# QI9-2605-A01.net
KiCad netlist of a schematic drawn in Altium Designer
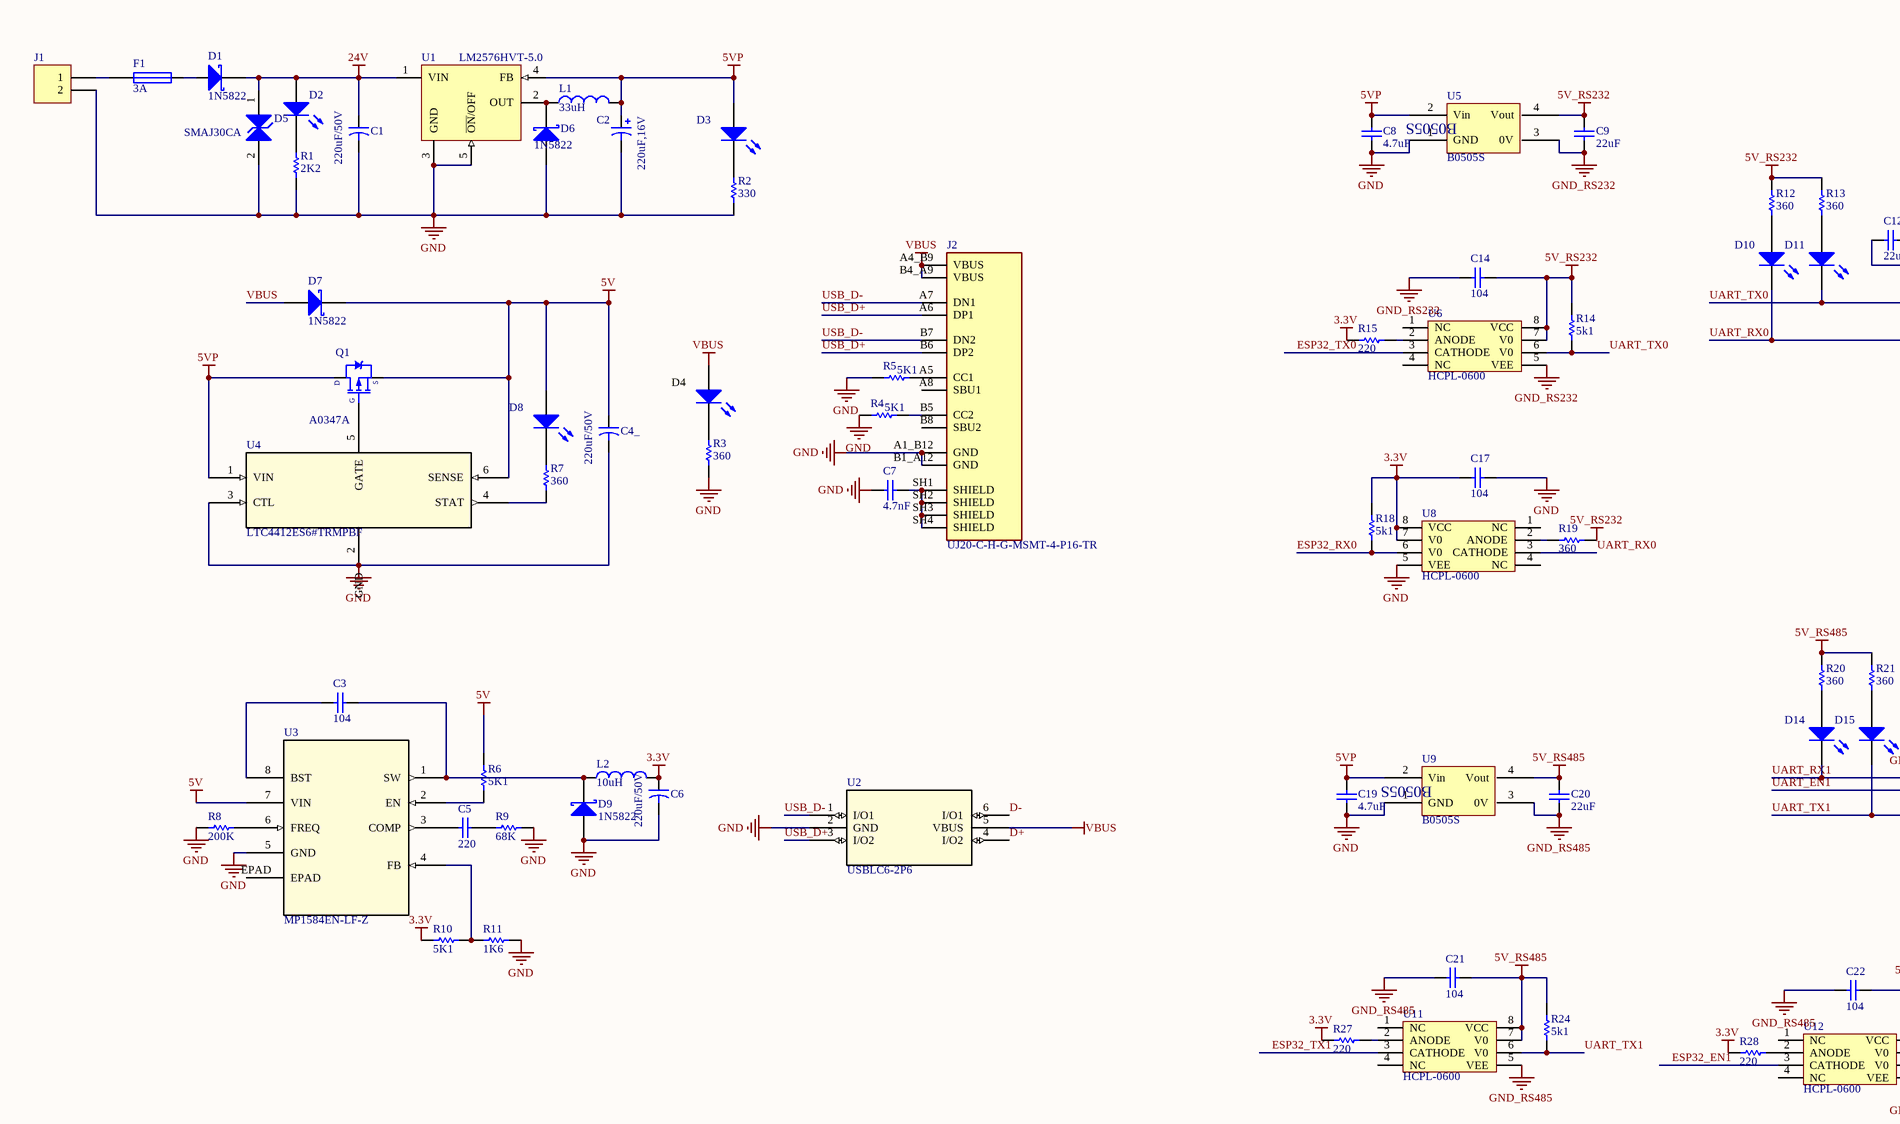
[diagram p0: QI9-2605-A01_.SchDoc, top left]
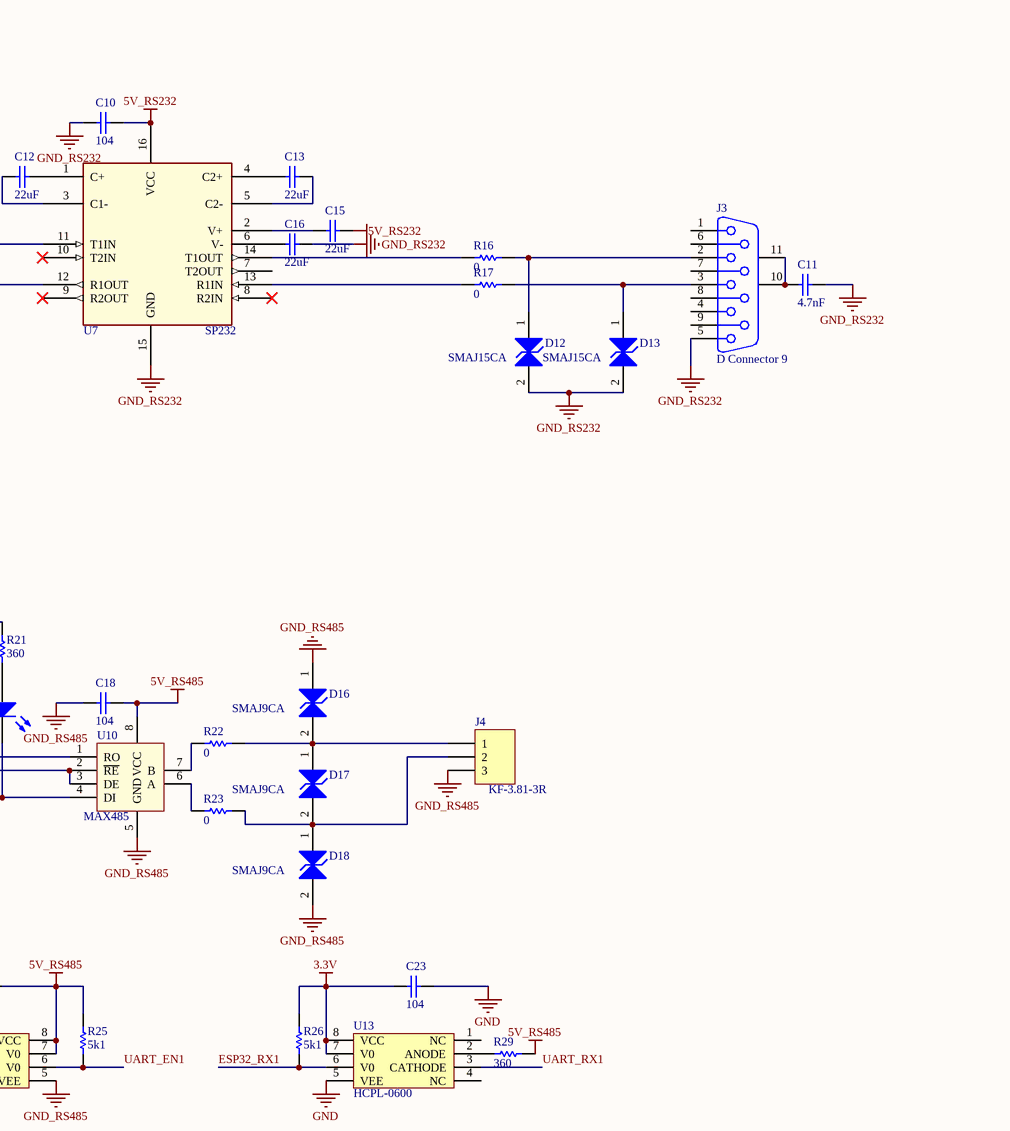
[diagram p1: QI9-2605-A01_.SchDoc, top right]
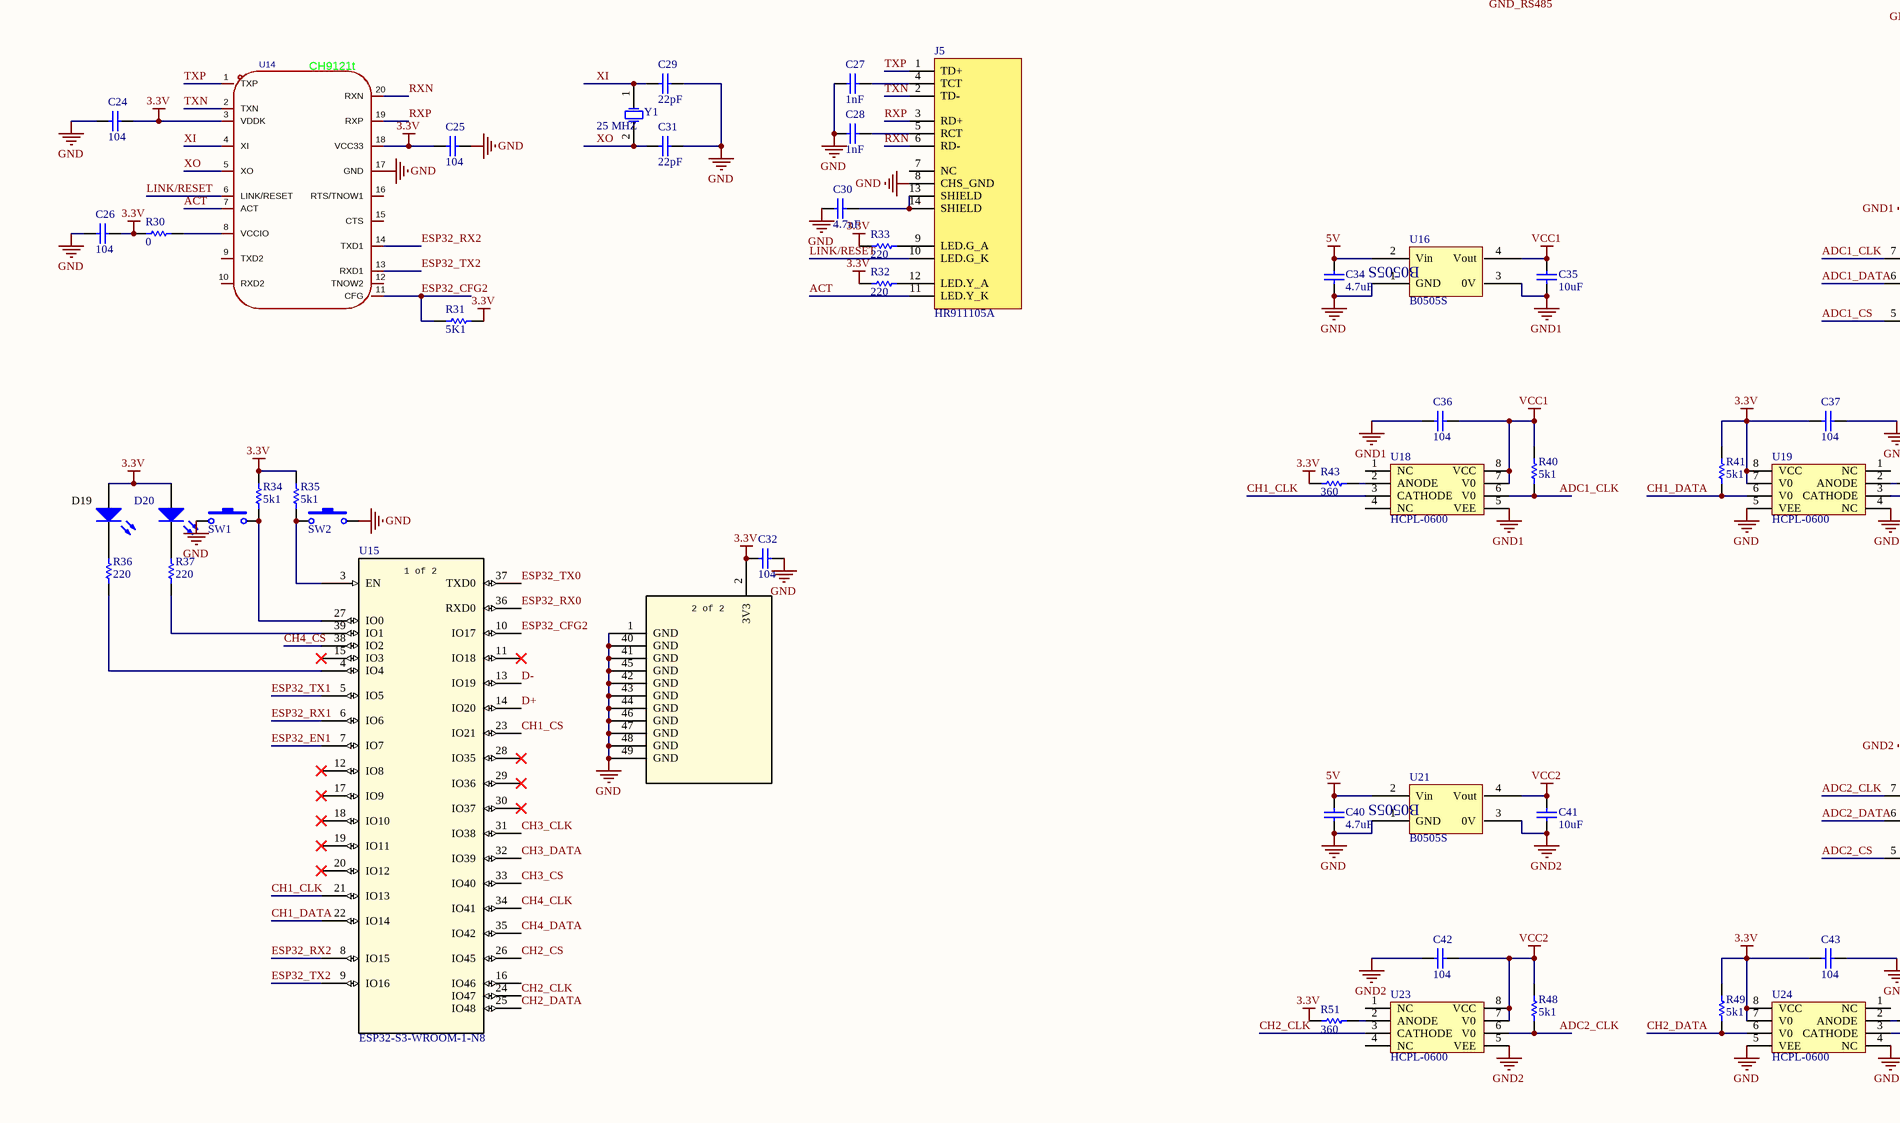
[diagram p2: QI9-2605-A01_.SchDoc, bottom left]
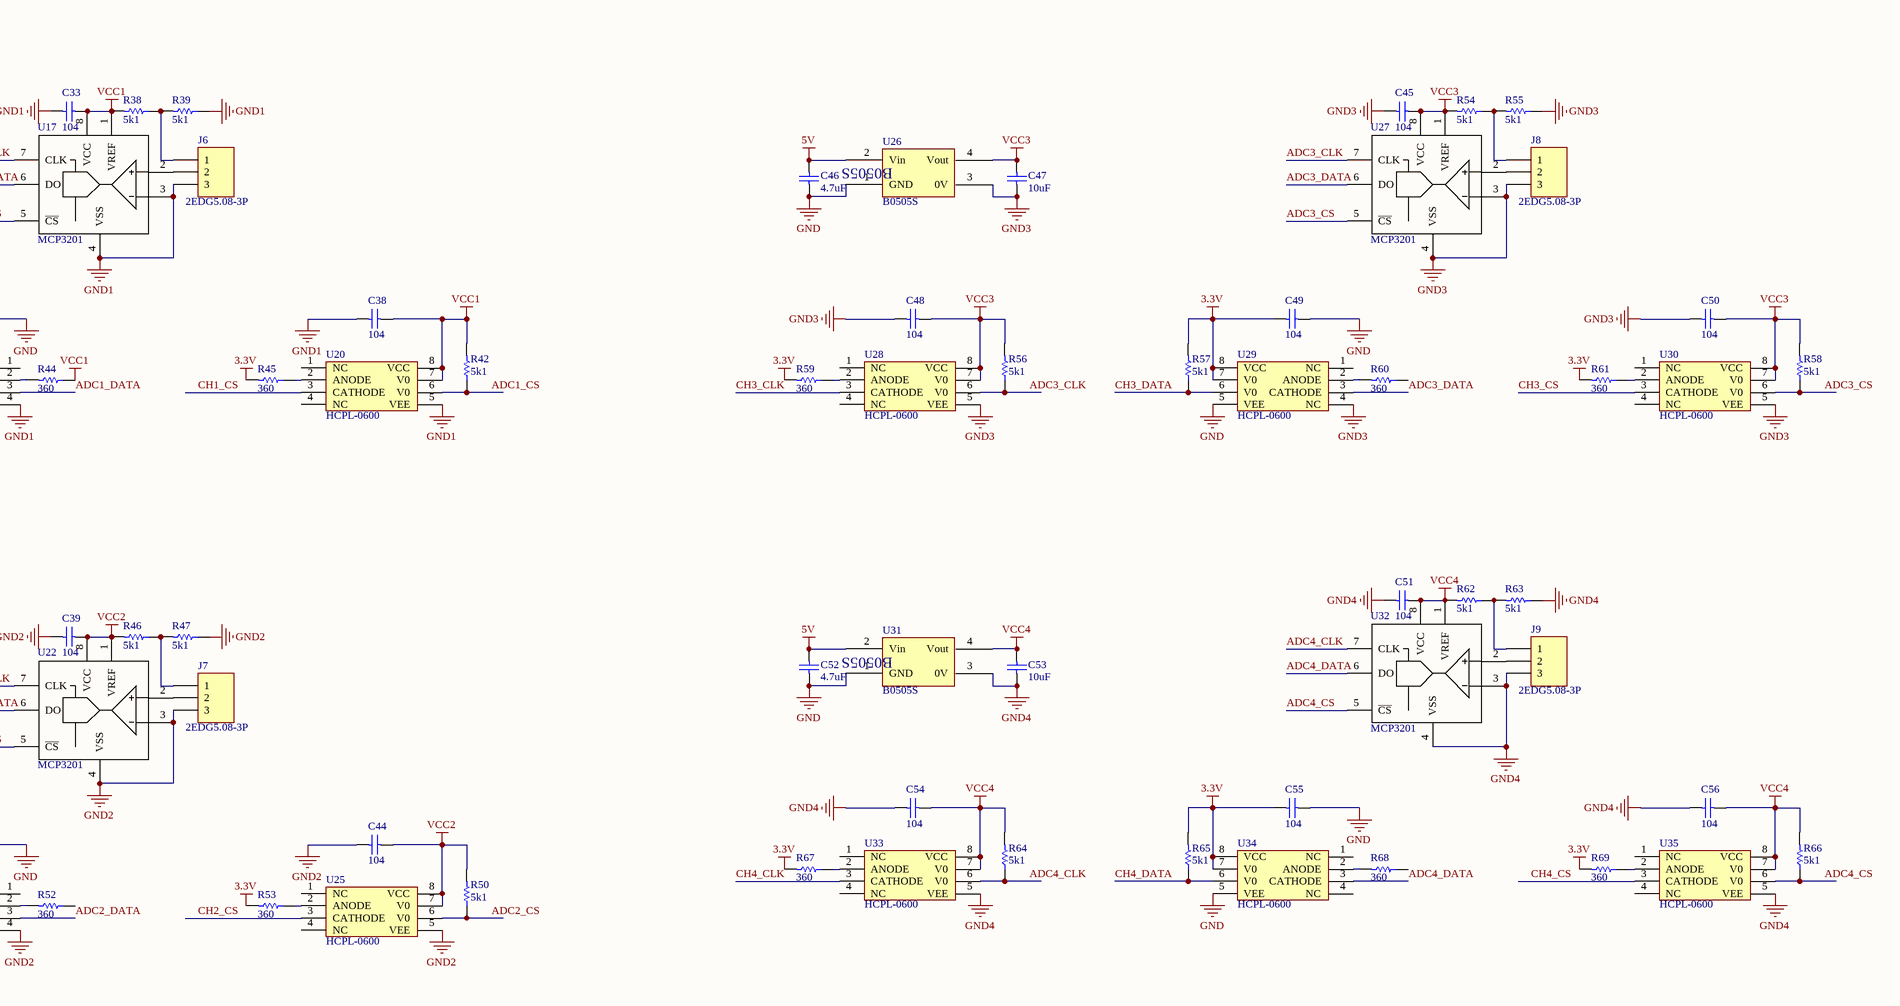
[diagram p3: QI9-2605-A01_.SchDoc, bottom right]

(export (version "E")
  (design (tool "Eeschema 10.0.6"))
  (components
    (comp (ref "C1")
      (value "220uF/50V")
      (footprint "C2")
      (description "Capacitor")
      (fields (field (name "Comment") "Cap2") (field (name "PUBLISHER") "Altium Limited"))
      (libsource (lib "Miscellaneous Devices") (part "Cap2"))
    )
    (comp (ref "C2")
      (value "220uF,16V")
      (footprint "c2")
      (description "Polarized Capacitor (Axial)")
      (fields (field (name "PUBLISHER") "Altium Limited"))
      (libsource (lib "StandardLIB") (part "Cap Pol 3mm"))
    )
    (comp (ref "C3")
      (value "104")
      (footprint "0805")
      (description "Capacitor")
      (fields (field (name "Comment") "Cap") (field (name "PUBLISHER") "Altium Limited"))
      (libsource (lib "Miscellaneous Devices") (part "Cap"))
    )
    (comp (ref "C4_")
      (value "220uF/50V")
      (footprint "C2")
      (description "Capacitor")
      (fields (field (name "Comment") "Cap2") (field (name "PUBLISHER") "Altium Limited"))
      (libsource (lib "Miscellaneous Devices") (part "Cap2"))
    )
    (comp (ref "C5")
      (value "220")
      (footprint "0805")
      (description "Capacitor")
      (fields (field (name "Comment") "Cap") (field (name "PUBLISHER") "Altium Limited"))
      (libsource (lib "Miscellaneous Devices") (part "Cap"))
    )
    (comp (ref "C6")
      (value "220uF/50V")
      (footprint "C2")
      (description "Capacitor")
      (fields (field (name "Comment") "Cap2") (field (name "PUBLISHER") "Altium Limited"))
      (libsource (lib "Miscellaneous Devices") (part "Cap2"))
    )
    (comp (ref "C7")
      (value "4.7nF")
      (footprint "0805")
      (description "Capacitor")
      (fields (field (name "Comment") "Cap") (field (name "PUBLISHER") "Altium Limited"))
      (libsource (lib "Miscellaneous Devices") (part "Cap"))
    )
    (comp (ref "C8")
      (value "4.7uF")
      (footprint "CP1/2")
      (description "Capacitor")
      (fields (field (name "Comment") "Cap") (field (name "PUBLISHER") "Altium Limited"))
      (libsource (lib "Miscellaneous Devices") (part "Cap"))
    )
    (comp (ref "C9")
      (value "22uF")
      (footprint "0805")
      (description "Capacitor")
      (fields (field (name "Comment") "Cap") (field (name "PUBLISHER") "Altium Limited"))
      (libsource (lib "Miscellaneous Devices") (part "Cap"))
    )
    (comp (ref "C10")
      (value "104")
      (footprint "0805")
      (description "Capacitor")
      (fields (field (name "Comment") "Cap") (field (name "PUBLISHER") "Altium Limited"))
      (libsource (lib "Miscellaneous Devices") (part "Cap"))
    )
    (comp (ref "C11")
      (value "4.7nF")
      (footprint "0805")
      (description "Capacitor")
      (fields (field (name "Comment") "Cap") (field (name "PUBLISHER") "Altium Limited"))
      (libsource (lib "Miscellaneous Devices") (part "Cap"))
    )
    (comp (ref "C12")
      (value "22uF")
      (footprint "0805")
      (description "Capacitor")
      (fields (field (name "Comment") "Cap") (field (name "PUBLISHER") "Altium Limited"))
      (libsource (lib "Miscellaneous Devices") (part "Cap"))
    )
    (comp (ref "C13")
      (value "22uF")
      (footprint "0805")
      (description "Capacitor")
      (fields (field (name "Comment") "Cap") (field (name "PUBLISHER") "Altium Limited"))
      (libsource (lib "Miscellaneous Devices") (part "Cap"))
    )
    (comp (ref "C14")
      (value "104")
      (footprint "0805")
      (description "Capacitor")
      (fields (field (name "Comment") "Cap") (field (name "PUBLISHER") "Altium Limited"))
      (libsource (lib "Miscellaneous Devices") (part "Cap"))
    )
    (comp (ref "C15")
      (value "22uF")
      (footprint "0805")
      (description "Capacitor")
      (fields (field (name "Comment") "Cap") (field (name "PUBLISHER") "Altium Limited"))
      (libsource (lib "Miscellaneous Devices") (part "Cap"))
    )
    (comp (ref "C16")
      (value "22uF")
      (footprint "0805")
      (description "Capacitor")
      (fields (field (name "Comment") "Cap") (field (name "PUBLISHER") "Altium Limited"))
      (libsource (lib "Miscellaneous Devices") (part "Cap"))
    )
    (comp (ref "C17")
      (value "104")
      (footprint "0805")
      (description "Capacitor")
      (fields (field (name "Comment") "Cap") (field (name "PUBLISHER") "Altium Limited"))
      (libsource (lib "Miscellaneous Devices") (part "Cap"))
    )
    (comp (ref "C18")
      (value "104")
      (footprint "0805")
      (description "Capacitor")
      (fields (field (name "Comment") "Cap") (field (name "PUBLISHER") "Altium Limited"))
      (libsource (lib "Miscellaneous Devices") (part "Cap"))
    )
    (comp (ref "C19")
      (value "4.7uF")
      (footprint "CP1/2")
      (description "Capacitor")
      (fields (field (name "Comment") "Cap") (field (name "PUBLISHER") "Altium Limited"))
      (libsource (lib "Miscellaneous Devices") (part "Cap"))
    )
    (comp (ref "C20")
      (value "22uF")
      (footprint "0805")
      (description "Capacitor")
      (fields (field (name "Comment") "Cap") (field (name "PUBLISHER") "Altium Limited"))
      (libsource (lib "Miscellaneous Devices") (part "Cap"))
    )
    (comp (ref "C21")
      (value "104")
      (footprint "0805")
      (description "Capacitor")
      (fields (field (name "Comment") "Cap") (field (name "PUBLISHER") "Altium Limited"))
      (libsource (lib "Miscellaneous Devices") (part "Cap"))
    )
    (comp (ref "C22")
      (value "104")
      (footprint "0805")
      (description "Capacitor")
      (fields (field (name "Comment") "Cap") (field (name "PUBLISHER") "Altium Limited"))
      (libsource (lib "Miscellaneous Devices") (part "Cap"))
    )
    (comp (ref "C23")
      (value "104")
      (footprint "0805")
      (description "Capacitor")
      (fields (field (name "Comment") "Cap") (field (name "PUBLISHER") "Altium Limited"))
      (libsource (lib "Miscellaneous Devices") (part "Cap"))
    )
    (comp (ref "C24")
      (value "104")
      (footprint "0805")
      (description "Capacitor")
      (fields (field (name "Comment") "Cap") (field (name "PUBLISHER") "Altium Limited"))
      (libsource (lib "Miscellaneous Devices") (part "Cap"))
    )
    (comp (ref "C25")
      (value "104")
      (footprint "0805")
      (description "Capacitor")
      (fields (field (name "Comment") "Cap") (field (name "PUBLISHER") "Altium Limited"))
      (libsource (lib "Miscellaneous Devices") (part "Cap"))
    )
    (comp (ref "C26")
      (value "104")
      (footprint "0805")
      (description "Capacitor")
      (fields (field (name "Comment") "Cap") (field (name "PUBLISHER") "Altium Limited"))
      (libsource (lib "Miscellaneous Devices") (part "Cap"))
    )
    (comp (ref "C27")
      (value "1nF")
      (footprint "0805")
      (description "Capacitor")
      (fields (field (name "Comment") "Cap") (field (name "PUBLISHER") "Altium Limited"))
      (libsource (lib "Miscellaneous Devices") (part "Cap"))
    )
    (comp (ref "C28")
      (value "1nF")
      (footprint "0805")
      (description "Capacitor")
      (fields (field (name "Comment") "Cap") (field (name "PUBLISHER") "Altium Limited"))
      (libsource (lib "Miscellaneous Devices") (part "Cap"))
    )
    (comp (ref "C29")
      (value "22pF")
      (footprint "0805")
      (description "Capacitor")
      (fields (field (name "Comment") "Cap") (field (name "PUBLISHER") "Altium Limited"))
      (libsource (lib "Miscellaneous Devices") (part "Cap"))
    )
    (comp (ref "C30")
      (value "4.7nF")
      (footprint "0805")
      (description "Capacitor")
      (fields (field (name "Comment") "Cap") (field (name "PUBLISHER") "Altium Limited"))
      (libsource (lib "Miscellaneous Devices") (part "Cap"))
    )
    (comp (ref "C31")
      (value "22pF")
      (footprint "0805")
      (description "Capacitor")
      (fields (field (name "Comment") "Cap") (field (name "PUBLISHER") "Altium Limited"))
      (libsource (lib "Miscellaneous Devices") (part "Cap"))
    )
    (comp (ref "C32")
      (value "104")
      (footprint "0805")
      (description "Capacitor")
      (fields (field (name "Comment") "Cap") (field (name "PUBLISHER") "Altium Limited"))
      (libsource (lib "Miscellaneous Devices") (part "Cap"))
    )
    (comp (ref "C33")
      (value "104")
      (footprint "0805")
      (description "Capacitor")
      (fields (field (name "Comment") "Cap") (field (name "PUBLISHER") "Altium Limited"))
      (libsource (lib "Miscellaneous Devices") (part "Cap"))
    )
    (comp (ref "C34")
      (value "4.7uF")
      (footprint "CP1/2")
      (description "Capacitor")
      (fields (field (name "Comment") "Cap") (field (name "PUBLISHER") "Altium Limited"))
      (libsource (lib "Miscellaneous Devices") (part "Cap"))
    )
    (comp (ref "C35")
      (value "10uF")
      (footprint "CP1/2")
      (description "Capacitor")
      (fields (field (name "Comment") "Cap") (field (name "PUBLISHER") "Altium Limited"))
      (libsource (lib "Miscellaneous Devices") (part "Cap"))
    )
    (comp (ref "C36")
      (value "104")
      (footprint "0805")
      (description "Capacitor")
      (fields (field (name "Comment") "Cap") (field (name "PUBLISHER") "Altium Limited"))
      (libsource (lib "Miscellaneous Devices") (part "Cap"))
    )
    (comp (ref "C37")
      (value "104")
      (footprint "0805")
      (description "Capacitor")
      (fields (field (name "Comment") "Cap") (field (name "PUBLISHER") "Altium Limited"))
      (libsource (lib "Miscellaneous Devices") (part "Cap"))
    )
    (comp (ref "C38")
      (value "104")
      (footprint "0805")
      (description "Capacitor")
      (fields (field (name "Comment") "Cap") (field (name "PUBLISHER") "Altium Limited"))
      (libsource (lib "Miscellaneous Devices") (part "Cap"))
    )
    (comp (ref "C39")
      (value "104")
      (footprint "0805")
      (description "Capacitor")
      (fields (field (name "Comment") "Cap") (field (name "PUBLISHER") "Altium Limited"))
      (libsource (lib "Miscellaneous Devices") (part "Cap"))
    )
    (comp (ref "C40")
      (value "4.7uF")
      (footprint "CP1/2")
      (description "Capacitor")
      (fields (field (name "Comment") "Cap") (field (name "PUBLISHER") "Altium Limited"))
      (libsource (lib "Miscellaneous Devices") (part "Cap"))
    )
    (comp (ref "C41")
      (value "10uF")
      (footprint "CP1/2")
      (description "Capacitor")
      (fields (field (name "Comment") "Cap") (field (name "PUBLISHER") "Altium Limited"))
      (libsource (lib "Miscellaneous Devices") (part "Cap"))
    )
    (comp (ref "C42")
      (value "104")
      (footprint "0805")
      (description "Capacitor")
      (fields (field (name "Comment") "Cap") (field (name "PUBLISHER") "Altium Limited"))
      (libsource (lib "Miscellaneous Devices") (part "Cap"))
    )
    (comp (ref "C43")
      (value "104")
      (footprint "0805")
      (description "Capacitor")
      (fields (field (name "Comment") "Cap") (field (name "PUBLISHER") "Altium Limited"))
      (libsource (lib "Miscellaneous Devices") (part "Cap"))
    )
    (comp (ref "C44")
      (value "104")
      (footprint "0805")
      (description "Capacitor")
      (fields (field (name "Comment") "Cap") (field (name "PUBLISHER") "Altium Limited"))
      (libsource (lib "Miscellaneous Devices") (part "Cap"))
    )
    (comp (ref "C45")
      (value "104")
      (footprint "0805")
      (description "Capacitor")
      (fields (field (name "Comment") "Cap") (field (name "PUBLISHER") "Altium Limited"))
      (libsource (lib "Miscellaneous Devices") (part "Cap"))
    )
    (comp (ref "C46")
      (value "4.7uF")
      (footprint "CP1/2")
      (description "Capacitor")
      (fields (field (name "Comment") "Cap") (field (name "PUBLISHER") "Altium Limited"))
      (libsource (lib "Miscellaneous Devices") (part "Cap"))
    )
    (comp (ref "C47")
      (value "10uF")
      (footprint "CP1/2")
      (description "Capacitor")
      (fields (field (name "Comment") "Cap") (field (name "PUBLISHER") "Altium Limited"))
      (libsource (lib "Miscellaneous Devices") (part "Cap"))
    )
    (comp (ref "C48")
      (value "104")
      (footprint "0805")
      (description "Capacitor")
      (fields (field (name "Comment") "Cap") (field (name "PUBLISHER") "Altium Limited"))
      (libsource (lib "Miscellaneous Devices") (part "Cap"))
    )
    (comp (ref "C49")
      (value "104")
      (footprint "0805")
      (description "Capacitor")
      (fields (field (name "Comment") "Cap") (field (name "PUBLISHER") "Altium Limited"))
      (libsource (lib "Miscellaneous Devices") (part "Cap"))
    )
    (comp (ref "C50")
      (value "104")
      (footprint "0805")
      (description "Capacitor")
      (fields (field (name "Comment") "Cap") (field (name "PUBLISHER") "Altium Limited"))
      (libsource (lib "Miscellaneous Devices") (part "Cap"))
    )
    (comp (ref "C51")
      (value "104")
      (footprint "0805")
      (description "Capacitor")
      (fields (field (name "Comment") "Cap") (field (name "PUBLISHER") "Altium Limited"))
      (libsource (lib "Miscellaneous Devices") (part "Cap"))
    )
    (comp (ref "C52")
      (value "4.7uF")
      (footprint "CP1/2")
      (description "Capacitor")
      (fields (field (name "Comment") "Cap") (field (name "PUBLISHER") "Altium Limited"))
      (libsource (lib "Miscellaneous Devices") (part "Cap"))
    )
    (comp (ref "C53")
      (value "10uF")
      (footprint "CP1/2")
      (description "Capacitor")
      (fields (field (name "Comment") "Cap") (field (name "PUBLISHER") "Altium Limited"))
      (libsource (lib "Miscellaneous Devices") (part "Cap"))
    )
    (comp (ref "C54")
      (value "104")
      (footprint "0805")
      (description "Capacitor")
      (fields (field (name "Comment") "Cap") (field (name "PUBLISHER") "Altium Limited"))
      (libsource (lib "Miscellaneous Devices") (part "Cap"))
    )
    (comp (ref "C55")
      (value "104")
      (footprint "0805")
      (description "Capacitor")
      (fields (field (name "Comment") "Cap") (field (name "PUBLISHER") "Altium Limited"))
      (libsource (lib "Miscellaneous Devices") (part "Cap"))
    )
    (comp (ref "C56")
      (value "104")
      (footprint "0805")
      (description "Capacitor")
      (fields (field (name "Comment") "Cap") (field (name "PUBLISHER") "Altium Limited"))
      (libsource (lib "Miscellaneous Devices") (part "Cap"))
    )
    (comp (ref "D1")
      (value "1N5822")
      (footprint "DIODE_DO214AC_SMA")
      (description "Schottky Diode")
      (fields (field (name "PUBLISHER") "Altium Limited"))
      (libsource (lib "Miscellaneous Devices") (part "D Schottky"))
    )
    (comp (ref "D2")
      (value "LED")
      (footprint "LED_0805_RED")
      (description "Typical INFRARED GaAs LED")
      (fields (field (name "PUBLISHER") "Altium Limited"))
      (libsource (lib "Miscellaneous Devices") (part "LED0"))
    )
    (comp (ref "D3")
      (value "LED")
      (footprint "LED_0805_RED")
      (description "Typical INFRARED GaAs LED")
      (fields (field (name "PUBLISHER") "Altium Limited"))
      (libsource (lib "Miscellaneous Devices") (part "LED0"))
    )
    (comp (ref "D4")
      (value "LED")
      (footprint "LED_0805_RED")
      (description "Typical INFRARED GaAs LED")
      (fields (field (name "PUBLISHER") "Altium Limited"))
      (libsource (lib "Miscellaneous Devices") (part "LED0"))
    )
    (comp (ref "D5")
      (value "SMAJ30CA")
      (footprint "SMA_STM")
      (description "TVS DIODE 30V 48.4V DO214AC")
      (fields (field (name "MPN") "SMAJ30A") (field (name "MFR") "Littelfuse Inc."))
      (libsource (lib "Cty1") (part "SMAJ30CA"))
    )
    (comp (ref "D6")
      (value "1N5822")
      (footprint "DIODE_DO214AC_SMA")
      (description "Schottky Diode")
      (fields (field (name "PUBLISHER") "Altium Limited"))
      (libsource (lib "Miscellaneous Devices") (part "D Schottky"))
    )
    (comp (ref "D7")
      (value "1N5822")
      (footprint "DIODE_DO214AC_SMA")
      (description "Schottky Diode")
      (fields (field (name "PUBLISHER") "Altium Limited"))
      (libsource (lib "Miscellaneous Devices") (part "D Schottky"))
    )
    (comp (ref "D8")
      (value "LED")
      (footprint "LED_0805_RED")
      (description "Typical INFRARED GaAs LED")
      (fields (field (name "PUBLISHER") "Altium Limited"))
      (libsource (lib "Miscellaneous Devices") (part "LED0"))
    )
    (comp (ref "D9")
      (value "1N5822")
      (footprint "DIODE_DO214AC_SMA")
      (description "Schottky Diode")
      (fields (field (name "PUBLISHER") "Altium Limited"))
      (libsource (lib "Miscellaneous Devices") (part "D Schottky"))
    )
    (comp (ref "D10")
      (value "LED")
      (footprint "LED_0805_RED")
      (description "Typical INFRARED GaAs LED")
      (fields (field (name "PUBLISHER") "Altium Limited"))
      (libsource (lib "Miscellaneous Devices") (part "LED0"))
    )
    (comp (ref "D11")
      (value "LED")
      (footprint "LED_0805_RED")
      (description "Typical INFRARED GaAs LED")
      (fields (field (name "PUBLISHER") "Altium Limited"))
      (libsource (lib "Miscellaneous Devices") (part "LED0"))
    )
    (comp (ref "D12")
      (value "SMAJ15CA")
      (footprint "SMA_STM")
      (description "TVS DIODE 30V 48.4V DO214AC")
      (fields (field (name "MPN") "SMAJ30A") (field (name "MFR") "Littelfuse Inc."))
      (libsource (lib "Cty1") (part "SMAJ30CA"))
    )
    (comp (ref "D13")
      (value "SMAJ15CA")
      (footprint "SMA_STM")
      (description "TVS DIODE 30V 48.4V DO214AC")
      (fields (field (name "MPN") "SMAJ30A") (field (name "MFR") "Littelfuse Inc."))
      (libsource (lib "Cty1") (part "SMAJ30CA"))
    )
    (comp (ref "D14")
      (value "LED")
      (footprint "LED_0805_RED")
      (description "Typical INFRARED GaAs LED")
      (fields (field (name "PUBLISHER") "Altium Limited"))
      (libsource (lib "Miscellaneous Devices") (part "LED0"))
    )
    (comp (ref "D15")
      (value "LED")
      (footprint "LED_0805_RED")
      (description "Typical INFRARED GaAs LED")
      (fields (field (name "PUBLISHER") "Altium Limited"))
      (libsource (lib "Miscellaneous Devices") (part "LED0"))
    )
    (comp (ref "D16")
      (value "SMAJ9CA")
      (footprint "SMA_STM")
      (description "TVS DIODE 30V 48.4V DO214AC")
      (fields (field (name "MPN") "SMAJ30A") (field (name "MFR") "Littelfuse Inc."))
      (libsource (lib "Cty1") (part "SMAJ30CA"))
    )
    (comp (ref "D17")
      (value "SMAJ9CA")
      (footprint "SMA_STM")
      (description "TVS DIODE 30V 48.4V DO214AC")
      (fields (field (name "MPN") "SMAJ30A") (field (name "MFR") "Littelfuse Inc."))
      (libsource (lib "Cty1") (part "SMAJ30CA"))
    )
    (comp (ref "D18")
      (value "SMAJ9CA")
      (footprint "SMA_STM")
      (description "TVS DIODE 30V 48.4V DO214AC")
      (fields (field (name "MPN") "SMAJ30A") (field (name "MFR") "Littelfuse Inc."))
      (libsource (lib "Cty1") (part "SMAJ30CA"))
    )
    (comp (ref "D19")
      (value "LED")
      (footprint "LED_0805_RED")
      (description "Typical INFRARED GaAs LED")
      (fields (field (name "PUBLISHER") "Altium Limited"))
      (libsource (lib "Miscellaneous Devices") (part "LED0"))
    )
    (comp (ref "D20")
      (value "LED")
      (footprint "LED_0805_RED")
      (description "Typical INFRARED GaAs LED")
      (fields (field (name "PUBLISHER") "Altium Limited"))
      (libsource (lib "Miscellaneous Devices") (part "LED0"))
    )
    (comp (ref "F1")
      (value "3A")
      (footprint "FUSE_1812(4532)")
      (description "Fuse")
      (fields (field (name "PUBLISHER") "Altium Limited"))
      (libsource (lib "Miscellaneous Devices") (part "Fuse 1"))
    )
    (comp (ref "J1")
      (value "KF-3.810-2R")
      (footprint "KF2-3.81")
      (description "Header, 2-Pin")
      (fields (field (name "PUBLISHER") "Altium Limited"))
      (libsource (lib "Miscellaneous Connectors") (part "Header 2"))
    )
    (comp (ref "J2")
      (value "UJ20-C-H-G-MSMT-4-P16-TR")
      (footprint "UJ20-C-H-G-MSMT-4-P16")
      (fields (field (name "MF") "{'manufacturer': u'Same Sky (Formerly CUI Devices)'}"))
      (libsource (lib "Cty1") (part "UJ20-C-H-G-MSMT-4-P16-TR"))
    )
    (comp (ref "J3")
      (value "D Connector 9")
      (footprint "DSUB1.385-2H9")
      (description "Receptacle Assembly, 9 Position, Right Angle")
      (fields (field (name "PUBLISHER") "Altium Limited"))
      (libsource (lib "BYTECH_HW_LIB_2019 (1)") (part "DB9_RA"))
    )
    (comp (ref "J4")
      (value "KF-3.81-3R")
      (footprint "KF3-3.81")
      (description "Header, 3-Pin")
      (fields (field (name "PUBLISHER") "Altium Limited"))
      (libsource (lib "Miscellaneous Connectors") (part "Header 3"))
    )
    (comp (ref "J5")
      (value "HR911105A")
      (footprint "HR911105A")
      (description "Hanrun HR911105A RJ-45 Connector")
      (fields (field (name "MFR") "HanRun"))
      (libsource (lib "BYTECH_HW_LIB_2019 (1)") (part "HR911105A"))
    )
    (comp (ref "J6")
      (value "2EDG5.08-3P")
      (footprint "CON 3 3EDG5.08")
      (description "Header, 3-Pin")
      (fields (field (name "PUBLISHER") "Altium Limited"))
      (libsource (lib "Miscellaneous Connectors") (part "Header 3"))
    )
    (comp (ref "J7")
      (value "2EDG5.08-3P")
      (footprint "CON 3 3EDG5.08")
      (description "Header, 3-Pin")
      (fields (field (name "PUBLISHER") "Altium Limited"))
      (libsource (lib "Miscellaneous Connectors") (part "Header 3"))
    )
    (comp (ref "J8")
      (value "2EDG5.08-3P")
      (footprint "CON 3 3EDG5.08")
      (description "Header, 3-Pin")
      (fields (field (name "PUBLISHER") "Altium Limited"))
      (libsource (lib "Miscellaneous Connectors") (part "Header 3"))
    )
    (comp (ref "J9")
      (value "2EDG5.08-3P")
      (footprint "CON 3 3EDG5.08")
      (description "Header, 3-Pin")
      (fields (field (name "PUBLISHER") "Altium Limited"))
      (libsource (lib "Miscellaneous Connectors") (part "Header 3"))
    )
    (comp (ref "L1")
      (value "33uH")
      (footprint "L1A")
      (description "Inductor")
      (fields (field (name "PUBLISHER") "Altium Limited"))
      (libsource (lib "Miscellaneous Devices") (part "Inductor"))
    )
    (comp (ref "L2")
      (value "10uH")
      (footprint "L1A")
      (description "Inductor")
      (fields (field (name "PUBLISHER") "Altium Limited"))
      (libsource (lib "Miscellaneous Devices") (part "Inductor"))
    )
    (comp (ref "Q1")
      (value "A0347A")
      (footprint "SOT23_")
      (description "HEXFET P-Channel Power MOSFET")
      (fields (field (name "PUBLISHER") "Altium Limited"))
      (libsource (lib "Cty1") (part "IRF9540"))
    )
    (comp (ref "R1")
      (value "2K2")
      (footprint "SM-RES-0805")
      (description "Resistor")
      (fields (field (name "Comment") "Res1") (field (name "PUBLISHER") "Altium Limited"))
      (libsource (lib "Miscellaneous Devices") (part "Res1"))
    )
    (comp (ref "R2")
      (value "330")
      (footprint "SM-RES-0805")
      (description "Resistor")
      (fields (field (name "Comment") "Res1") (field (name "PUBLISHER") "Altium Limited"))
      (libsource (lib "Miscellaneous Devices") (part "Res1"))
    )
    (comp (ref "R3")
      (value "360")
      (footprint "SM-RES-0805")
      (description "Resistor")
      (fields (field (name "Comment") "Res1") (field (name "PUBLISHER") "Altium Limited"))
      (libsource (lib "Miscellaneous Devices") (part "Res1"))
    )
    (comp (ref "R4")
      (value "5K1")
      (footprint "SM-RES-0805")
      (description "Resistor")
      (fields (field (name "Comment") "Res1") (field (name "PUBLISHER") "Altium Limited"))
      (libsource (lib "Miscellaneous Devices") (part "Res1"))
    )
    (comp (ref "R5")
      (value "5K1")
      (footprint "SM-RES-0805")
      (description "Resistor")
      (fields (field (name "Comment") "Res1") (field (name "PUBLISHER") "Altium Limited"))
      (libsource (lib "Miscellaneous Devices") (part "Res1"))
    )
    (comp (ref "R6")
      (value "5K1")
      (footprint "SM-RES-0805")
      (description "Resistor")
      (fields (field (name "Comment") "Res1") (field (name "PUBLISHER") "Altium Limited"))
      (libsource (lib "Miscellaneous Devices") (part "Res1"))
    )
    (comp (ref "R7")
      (value "360")
      (footprint "SM-RES-0805")
      (description "Resistor")
      (fields (field (name "Comment") "Res1") (field (name "PUBLISHER") "Altium Limited"))
      (libsource (lib "Miscellaneous Devices") (part "Res1"))
    )
    (comp (ref "R8")
      (value "200K")
      (footprint "SM-RES-0805")
      (description "Resistor")
      (fields (field (name "Comment") "Res1") (field (name "PUBLISHER") "Altium Limited"))
      (libsource (lib "Miscellaneous Devices") (part "Res1"))
    )
    (comp (ref "R9")
      (value "68K")
      (footprint "SM-RES-0805")
      (description "Resistor")
      (fields (field (name "Comment") "Res1") (field (name "PUBLISHER") "Altium Limited"))
      (libsource (lib "Miscellaneous Devices") (part "Res1"))
    )
    (comp (ref "R10")
      (value "5K1")
      (footprint "SM-RES-0805")
      (description "Resistor")
      (fields (field (name "Comment") "Res1") (field (name "PUBLISHER") "Altium Limited"))
      (libsource (lib "Miscellaneous Devices") (part "Res1"))
    )
    (comp (ref "R11")
      (value "1K6")
      (footprint "SM-RES-0805")
      (description "Resistor")
      (fields (field (name "Comment") "Res1") (field (name "PUBLISHER") "Altium Limited"))
      (libsource (lib "Miscellaneous Devices") (part "Res1"))
    )
    (comp (ref "R12")
      (value "360")
      (footprint "SM-RES-0805")
      (description "Resistor")
      (fields (field (name "Comment") "Res1") (field (name "PUBLISHER") "Altium Limited"))
      (libsource (lib "Miscellaneous Devices") (part "Res1"))
    )
    (comp (ref "R13")
      (value "360")
      (footprint "SM-RES-0805")
      (description "Resistor")
      (fields (field (name "Comment") "Res1") (field (name "PUBLISHER") "Altium Limited"))
      (libsource (lib "Miscellaneous Devices") (part "Res1"))
    )
    (comp (ref "R14")
      (value "5k1")
      (footprint "SM-RES-0805")
      (description "Resistor")
      (fields (field (name "Comment") "Res1") (field (name "PUBLISHER") "Altium Limited"))
      (libsource (lib "Miscellaneous Devices") (part "Res1"))
    )
    (comp (ref "R15")
      (value "220")
      (footprint "SM-RES-0805")
      (description "Resistor")
      (fields (field (name "Comment") "Res1") (field (name "PUBLISHER") "Altium Limited"))
      (libsource (lib "Miscellaneous Devices") (part "Res1"))
    )
    (comp (ref "R16")
      (value "0")
      (footprint "SM-RES-0805")
      (description "Resistor")
      (fields (field (name "Comment") "Res1") (field (name "PUBLISHER") "Altium Limited"))
      (libsource (lib "Miscellaneous Devices") (part "Res1"))
    )
    (comp (ref "R17")
      (value "0")
      (footprint "SM-RES-0805")
      (description "Resistor")
      (fields (field (name "Comment") "Res1") (field (name "PUBLISHER") "Altium Limited"))
      (libsource (lib "Miscellaneous Devices") (part "Res1"))
    )
    (comp (ref "R18")
      (value "5k1")
      (footprint "SM-RES-0805")
      (description "Resistor")
      (fields (field (name "Comment") "Res1") (field (name "PUBLISHER") "Altium Limited"))
      (libsource (lib "Miscellaneous Devices") (part "Res1"))
    )
    (comp (ref "R19")
      (value "360")
      (footprint "SM-RES-0805")
      (description "Resistor")
      (fields (field (name "Comment") "Res1") (field (name "PUBLISHER") "Altium Limited"))
      (libsource (lib "Miscellaneous Devices") (part "Res1"))
    )
    (comp (ref "R20")
      (value "360")
      (footprint "SM-RES-0805")
      (description "Resistor")
      (fields (field (name "Comment") "Res1") (field (name "PUBLISHER") "Altium Limited"))
      (libsource (lib "Miscellaneous Devices") (part "Res1"))
    )
    (comp (ref "R21")
      (value "360")
      (footprint "SM-RES-0805")
      (description "Resistor")
      (fields (field (name "Comment") "Res1") (field (name "PUBLISHER") "Altium Limited"))
      (libsource (lib "Miscellaneous Devices") (part "Res1"))
    )
    (comp (ref "R22")
      (value "0")
      (footprint "SM-RES-0805")
      (description "Resistor")
      (fields (field (name "Comment") "Res1") (field (name "PUBLISHER") "Altium Limited"))
      (libsource (lib "Miscellaneous Devices") (part "Res1"))
    )
    (comp (ref "R23")
      (value "0")
      (footprint "SM-RES-0805")
      (description "Resistor")
      (fields (field (name "Comment") "Res1") (field (name "PUBLISHER") "Altium Limited"))
      (libsource (lib "Miscellaneous Devices") (part "Res1"))
    )
    (comp (ref "R24")
      (value "5k1")
      (footprint "SM-RES-0805")
      (description "Resistor")
      (fields (field (name "Comment") "Res1") (field (name "PUBLISHER") "Altium Limited"))
      (libsource (lib "Miscellaneous Devices") (part "Res1"))
    )
    (comp (ref "R25")
      (value "5k1")
      (footprint "SM-RES-0805")
      (description "Resistor")
      (fields (field (name "Comment") "Res1") (field (name "PUBLISHER") "Altium Limited"))
      (libsource (lib "Miscellaneous Devices") (part "Res1"))
    )
    (comp (ref "R26")
      (value "5k1")
      (footprint "SM-RES-0805")
      (description "Resistor")
      (fields (field (name "Comment") "Res1") (field (name "PUBLISHER") "Altium Limited"))
      (libsource (lib "Miscellaneous Devices") (part "Res1"))
    )
    (comp (ref "R27")
      (value "220")
      (footprint "SM-RES-0805")
      (description "Resistor")
      (fields (field (name "Comment") "Res1") (field (name "PUBLISHER") "Altium Limited"))
      (libsource (lib "Miscellaneous Devices") (part "Res1"))
    )
    (comp (ref "R28")
      (value "220")
      (footprint "SM-RES-0805")
      (description "Resistor")
      (fields (field (name "Comment") "Res1") (field (name "PUBLISHER") "Altium Limited"))
      (libsource (lib "Miscellaneous Devices") (part "Res1"))
    )
    (comp (ref "R29")
      (value "360")
      (footprint "SM-RES-0805")
      (description "Resistor")
      (fields (field (name "Comment") "Res1") (field (name "PUBLISHER") "Altium Limited"))
      (libsource (lib "Miscellaneous Devices") (part "Res1"))
    )
    (comp (ref "R30")
      (value "0")
      (footprint "SM-RES-0805")
      (description "Resistor")
      (fields (field (name "Comment") "Res1") (field (name "PUBLISHER") "Altium Limited"))
      (libsource (lib "Miscellaneous Devices") (part "Res1"))
    )
    (comp (ref "R31")
      (value "5K1")
      (footprint "SM-RES-0805")
      (description "Resistor")
      (fields (field (name "Comment") "Res1") (field (name "PUBLISHER") "Altium Limited"))
      (libsource (lib "Miscellaneous Devices") (part "Res1"))
    )
    (comp (ref "R32")
      (value "220")
      (footprint "SM-RES-0805")
      (description "Resistor")
      (fields (field (name "Comment") "Res1") (field (name "PUBLISHER") "Altium Limited"))
      (libsource (lib "Miscellaneous Devices") (part "Res1"))
    )
    (comp (ref "R33")
      (value "220")
      (footprint "SM-RES-0805")
      (description "Resistor")
      (fields (field (name "Comment") "Res1") (field (name "PUBLISHER") "Altium Limited"))
      (libsource (lib "Miscellaneous Devices") (part "Res1"))
    )
    (comp (ref "R34")
      (value "5k1")
      (footprint "SM-RES-0805")
      (description "Resistor")
      (fields (field (name "Comment") "Res1") (field (name "PUBLISHER") "Altium Limited"))
      (libsource (lib "Miscellaneous Devices") (part "Res1"))
    )
    (comp (ref "R35")
      (value "5k1")
      (footprint "SM-RES-0805")
      (description "Resistor")
      (fields (field (name "Comment") "Res1") (field (name "PUBLISHER") "Altium Limited"))
      (libsource (lib "Miscellaneous Devices") (part "Res1"))
    )
    (comp (ref "R36")
      (value "220")
      (footprint "SM-RES-0805")
      (description "Resistor")
      (fields (field (name "Comment") "Res1") (field (name "PUBLISHER") "Altium Limited"))
      (libsource (lib "Miscellaneous Devices") (part "Res1"))
    )
    (comp (ref "R37")
      (value "220")
      (footprint "SM-RES-0805")
      (description "Resistor")
      (fields (field (name "Comment") "Res1") (field (name "PUBLISHER") "Altium Limited"))
      (libsource (lib "Miscellaneous Devices") (part "Res1"))
    )
    (comp (ref "R38")
      (value "5k1")
      (footprint "SM-RES-0805")
      (description "Resistor")
      (fields (field (name "Comment") "Res1") (field (name "PUBLISHER") "Altium Limited"))
      (libsource (lib "Miscellaneous Devices") (part "Res1"))
    )
    (comp (ref "R39")
      (value "5k1")
      (footprint "SM-RES-0805")
      (description "Resistor")
      (fields (field (name "Comment") "Res1") (field (name "PUBLISHER") "Altium Limited"))
      (libsource (lib "Miscellaneous Devices") (part "Res1"))
    )
    (comp (ref "R40")
      (value "5k1")
      (footprint "SM-RES-0805")
      (description "Resistor")
      (fields (field (name "Comment") "Res1") (field (name "PUBLISHER") "Altium Limited"))
      (libsource (lib "Miscellaneous Devices") (part "Res1"))
    )
    (comp (ref "R41")
      (value "5k1")
      (footprint "SM-RES-0805")
      (description "Resistor")
      (fields (field (name "Comment") "Res1") (field (name "PUBLISHER") "Altium Limited"))
      (libsource (lib "Miscellaneous Devices") (part "Res1"))
    )
    (comp (ref "R42")
      (value "5k1")
      (footprint "SM-RES-0805")
      (description "Resistor")
      (fields (field (name "Comment") "Res1") (field (name "PUBLISHER") "Altium Limited"))
      (libsource (lib "Miscellaneous Devices") (part "Res1"))
    )
    (comp (ref "R43")
      (value "360")
      (footprint "SM-RES-0805")
      (description "Resistor")
      (fields (field (name "Comment") "Res1") (field (name "PUBLISHER") "Altium Limited"))
      (libsource (lib "Miscellaneous Devices") (part "Res1"))
    )
    (comp (ref "R44")
      (value "360")
      (footprint "SM-RES-0805")
      (description "Resistor")
      (fields (field (name "Comment") "Res1") (field (name "PUBLISHER") "Altium Limited"))
      (libsource (lib "Miscellaneous Devices") (part "Res1"))
    )
    (comp (ref "R45")
      (value "360")
      (footprint "SM-RES-0805")
      (description "Resistor")
      (fields (field (name "Comment") "Res1") (field (name "PUBLISHER") "Altium Limited"))
      (libsource (lib "Miscellaneous Devices") (part "Res1"))
    )
    (comp (ref "R46")
      (value "5k1")
      (footprint "SM-RES-0805")
      (description "Resistor")
      (fields (field (name "Comment") "Res1") (field (name "PUBLISHER") "Altium Limited"))
      (libsource (lib "Miscellaneous Devices") (part "Res1"))
    )
    (comp (ref "R47")
      (value "5k1")
      (footprint "SM-RES-0805")
      (description "Resistor")
      (fields (field (name "Comment") "Res1") (field (name "PUBLISHER") "Altium Limited"))
      (libsource (lib "Miscellaneous Devices") (part "Res1"))
    )
    (comp (ref "R48")
      (value "5k1")
      (footprint "SM-RES-0805")
      (description "Resistor")
      (fields (field (name "Comment") "Res1") (field (name "PUBLISHER") "Altium Limited"))
      (libsource (lib "Miscellaneous Devices") (part "Res1"))
    )
    (comp (ref "R49")
      (value "5k1")
      (footprint "SM-RES-0805")
      (description "Resistor")
      (fields (field (name "Comment") "Res1") (field (name "PUBLISHER") "Altium Limited"))
      (libsource (lib "Miscellaneous Devices") (part "Res1"))
    )
    (comp (ref "R50")
      (value "5k1")
      (footprint "SM-RES-0805")
      (description "Resistor")
      (fields (field (name "Comment") "Res1") (field (name "PUBLISHER") "Altium Limited"))
      (libsource (lib "Miscellaneous Devices") (part "Res1"))
    )
    (comp (ref "R51")
      (value "360")
      (footprint "SM-RES-0805")
      (description "Resistor")
      (fields (field (name "Comment") "Res1") (field (name "PUBLISHER") "Altium Limited"))
      (libsource (lib "Miscellaneous Devices") (part "Res1"))
    )
    (comp (ref "R52")
      (value "360")
      (footprint "SM-RES-0805")
      (description "Resistor")
      (fields (field (name "Comment") "Res1") (field (name "PUBLISHER") "Altium Limited"))
      (libsource (lib "Miscellaneous Devices") (part "Res1"))
    )
    (comp (ref "R53")
      (value "360")
      (footprint "SM-RES-0805")
      (description "Resistor")
      (fields (field (name "Comment") "Res1") (field (name "PUBLISHER") "Altium Limited"))
      (libsource (lib "Miscellaneous Devices") (part "Res1"))
    )
    (comp (ref "R54")
      (value "5k1")
      (footprint "SM-RES-0805")
      (description "Resistor")
      (fields (field (name "Comment") "Res1") (field (name "PUBLISHER") "Altium Limited"))
      (libsource (lib "Miscellaneous Devices") (part "Res1"))
    )
    (comp (ref "R55")
      (value "5k1")
      (footprint "SM-RES-0805")
      (description "Resistor")
      (fields (field (name "Comment") "Res1") (field (name "PUBLISHER") "Altium Limited"))
      (libsource (lib "Miscellaneous Devices") (part "Res1"))
    )
    (comp (ref "R56")
      (value "5k1")
      (footprint "SM-RES-0805")
      (description "Resistor")
      (fields (field (name "Comment") "Res1") (field (name "PUBLISHER") "Altium Limited"))
      (libsource (lib "Miscellaneous Devices") (part "Res1"))
    )
    (comp (ref "R57")
      (value "5k1")
      (footprint "SM-RES-0805")
      (description "Resistor")
      (fields (field (name "Comment") "Res1") (field (name "PUBLISHER") "Altium Limited"))
      (libsource (lib "Miscellaneous Devices") (part "Res1"))
    )
    (comp (ref "R58")
      (value "5k1")
      (footprint "SM-RES-0805")
      (description "Resistor")
      (fields (field (name "Comment") "Res1") (field (name "PUBLISHER") "Altium Limited"))
      (libsource (lib "Miscellaneous Devices") (part "Res1"))
    )
    (comp (ref "R59")
      (value "360")
      (footprint "SM-RES-0805")
      (description "Resistor")
      (fields (field (name "Comment") "Res1") (field (name "PUBLISHER") "Altium Limited"))
      (libsource (lib "Miscellaneous Devices") (part "Res1"))
    )
    (comp (ref "R60")
      (value "360")
      (footprint "SM-RES-0805")
      (description "Resistor")
      (fields (field (name "Comment") "Res1") (field (name "PUBLISHER") "Altium Limited"))
      (libsource (lib "Miscellaneous Devices") (part "Res1"))
    )
    (comp (ref "R61")
      (value "360")
      (footprint "SM-RES-0805")
      (description "Resistor")
      (fields (field (name "Comment") "Res1") (field (name "PUBLISHER") "Altium Limited"))
      (libsource (lib "Miscellaneous Devices") (part "Res1"))
    )
    (comp (ref "R62")
      (value "5k1")
      (footprint "SM-RES-0805")
      (description "Resistor")
      (fields (field (name "Comment") "Res1") (field (name "PUBLISHER") "Altium Limited"))
      (libsource (lib "Miscellaneous Devices") (part "Res1"))
    )
    (comp (ref "R63")
      (value "5k1")
      (footprint "SM-RES-0805")
      (description "Resistor")
      (fields (field (name "Comment") "Res1") (field (name "PUBLISHER") "Altium Limited"))
      (libsource (lib "Miscellaneous Devices") (part "Res1"))
    )
    (comp (ref "R64")
      (value "5k1")
      (footprint "SM-RES-0805")
      (description "Resistor")
      (fields (field (name "Comment") "Res1") (field (name "PUBLISHER") "Altium Limited"))
      (libsource (lib "Miscellaneous Devices") (part "Res1"))
    )
    (comp (ref "R65")
      (value "5k1")
      (footprint "SM-RES-0805")
      (description "Resistor")
      (fields (field (name "Comment") "Res1") (field (name "PUBLISHER") "Altium Limited"))
      (libsource (lib "Miscellaneous Devices") (part "Res1"))
    )
    (comp (ref "R66")
      (value "5k1")
      (footprint "SM-RES-0805")
      (description "Resistor")
      (fields (field (name "Comment") "Res1") (field (name "PUBLISHER") "Altium Limited"))
      (libsource (lib "Miscellaneous Devices") (part "Res1"))
    )
    (comp (ref "R67")
      (value "360")
      (footprint "SM-RES-0805")
      (description "Resistor")
      (fields (field (name "Comment") "Res1") (field (name "PUBLISHER") "Altium Limited"))
      (libsource (lib "Miscellaneous Devices") (part "Res1"))
    )
    (comp (ref "R68")
      (value "360")
      (footprint "SM-RES-0805")
      (description "Resistor")
      (fields (field (name "Comment") "Res1") (field (name "PUBLISHER") "Altium Limited"))
      (libsource (lib "Miscellaneous Devices") (part "Res1"))
    )
    (comp (ref "R69")
      (value "360")
      (footprint "SM-RES-0805")
      (description "Resistor")
      (fields (field (name "Comment") "Res1") (field (name "PUBLISHER") "Altium Limited"))
      (libsource (lib "Miscellaneous Devices") (part "Res1"))
    )
    (comp (ref "SW1")
      (value "SW-SMD")
      (footprint "SW-SMD")
      (description "Switch")
      (fields (field (name "PUBLISHER") "Altium Limited"))
      (libsource (lib "Cty1") (part "SW-SMD"))
    )
    (comp (ref "SW2")
      (value "SW-SMD")
      (footprint "SW-SMD")
      (description "Switch")
      (fields (field (name "PUBLISHER") "Altium Limited"))
      (libsource (lib "Cty1") (part "SW-SMD"))
    )
    (comp (ref "U1")
      (value "LM2576HVT-5.0")
      (footprint "T05")
      (description "SIMPLE SWITCHER; 3A Step-Down Voltage Regulator")
      (fields
        (field (name "MANUFACTURER") "National Semiconductor")
        (field (name "DIGIKEYPARTNUMBER") "LM2576HVT-5.0-ND")
        (field (name "PUBLISHER") "Altium Limited")
      )
      (libsource (lib "NSC Switcher") (part "LM2576HVT-5.0"))
    )
    (comp (ref "U2")
      (value "USBLC6-2P6")
      (footprint "SOT-666_STM")
      (description "ESD Protection for USB 2.0 High Speed")
      (fields (field (name "COPYRIGHT") "Copyright (C) 2025 Ultra Librarian. All rights reserved."))
      (libsource (lib "Cty1") (part "USBLC6-2P6"))
    )
    (comp (ref "U3")
      (value "MP1584EN-LF-Z")
      (footprint "SOIC8E_MPS")
      (description "<p>3A 1.5MHz 28V Step-Down Converter</p>")
      (fields (field (name "COPYRIGHT") "Copyright (C) 2026 Ultra Librarian. All rights reserved."))
      (libsource (lib "Cty1") (part "MP1584EN-LF-Z"))
    )
    (comp (ref "U4")
      (value "LTC4412ES6#TRMPBF")
      (footprint "SOT-6_S_LIT")
      (description "Low Loss PowerPathâ„¢ Controller in ThinSOT")
      (fields (field (name "COPYRIGHT") "Copyright (C) 2025 Ultra Librarian. All rights reserved."))
      (libsource (lib "Cty1") (part "LTC4412ES6TRMPBF"))
    )
    (comp (ref "U5")
      (value "B0505S")
      (footprint "B0505S")
      (description "Cắm")
      (libsource (lib "IC") (part "B0505S"))
    )
    (comp (ref "U6")
      (value "HCPL-0600")
      (footprint "SOIC8_50_328_25X90_SMT")
      (description "2.5A Gate Driver Optical Coupling 3750Vrms 1 Channel 8-DIP Gull Wing")
      (fields
        (field (name "MANUFACTURER") "Broadcom Avago")
        (field (name "MANUFACTURER PART NUMBER") "HCPL-3120-500E")
      )
      (libsource (lib "") (part "IC_HCPL-3120-500E_1"))
    )
    (comp (ref "U7")
      (value "SP232")
      (footprint "soic16_m")
      (description "Enhanced RS-232 Line Drivers/Receivers")
      (fields (field (name "MANUFACTURER") "Sipex") (field (name "PUBLISHER") "Hoang Nguyen"))
      (libsource (lib "hphonglib") (part "SP232"))
    )
    (comp (ref "U8")
      (value "HCPL-0600")
      (footprint "SOIC8_50_328_25X90_SMT")
      (description "2.5A Gate Driver Optical Coupling 3750Vrms 1 Channel 8-DIP Gull Wing")
      (fields
        (field (name "MANUFACTURER") "Broadcom Avago")
        (field (name "MANUFACTURER PART NUMBER") "HCPL-3120-500E")
      )
      (libsource (lib "IC") (part "IC_HCPL-3120-500E"))
    )
    (comp (ref "U9")
      (value "B0505S")
      (footprint "B0505S")
      (description "Cắm")
      (libsource (lib "IC") (part "B0505S"))
    )
    (comp (ref "U10")
      (value "MAX485")
      (footprint "DIP8")
      (description "RS232 - RS485 (Same sn75176)")
      (libsource (lib "altium-import") (part "root_0_MAX485_"))
    )
    (comp (ref "U11")
      (value "HCPL-0600")
      (footprint "SOIC8_50_328_25X90_SMT")
      (description "2.5A Gate Driver Optical Coupling 3750Vrms 1 Channel 8-DIP Gull Wing")
      (fields
        (field (name "MANUFACTURER") "Broadcom Avago")
        (field (name "MANUFACTURER PART NUMBER") "HCPL-3120-500E")
      )
      (libsource (lib "") (part "IC_HCPL-3120-500E_1"))
    )
    (comp (ref "U12")
      (value "HCPL-0600")
      (footprint "SOIC8_50_328_25X90_SMT")
      (description "2.5A Gate Driver Optical Coupling 3750Vrms 1 Channel 8-DIP Gull Wing")
      (fields
        (field (name "MANUFACTURER") "Broadcom Avago")
        (field (name "MANUFACTURER PART NUMBER") "HCPL-3120-500E")
      )
      (libsource (lib "") (part "IC_HCPL-3120-500E_1"))
    )
    (comp (ref "U13")
      (value "HCPL-0600")
      (footprint "SOIC8_50_328_25X90_SMT")
      (description "2.5A Gate Driver Optical Coupling 3750Vrms 1 Channel 8-DIP Gull Wing")
      (fields
        (field (name "MANUFACTURER") "Broadcom Avago")
        (field (name "MANUFACTURER PART NUMBER") "HCPL-3120-500E")
      )
      (libsource (lib "IC") (part "IC_HCPL-3120-500E"))
    )
    (comp (ref "U14")
      (value "CH9121t")
      (footprint "tssop20")
      (fields (field (name "MANUFACTURER") "WCH(南京沁恒)") (field (name "MANUFACTURERPART") "CH9121T"))
      (libsource (lib "altium-import") (part "root_0_ch9121t_c45354919_"))
    )
    (comp (ref "U15")
      (value "ESP32-S3-WROOM-1-N8")
      (footprint "ESP32-S3-WROOM-1_EXP")
      (description "Description")
      (fields (field (name "COPYRIGHT") "Copyright (C) 2026 Ultra Librarian. All rights reserved."))
      (libsource (lib "Cty1") (part "ESP32-S3-WROOM-1"))
    )
    (comp (ref "U16")
      (value "B0505S")
      (footprint "B0505S")
      (description "Cắm")
      (libsource (lib "IC") (part "B0505S"))
    )
    (comp (ref "U17")
      (value "MCP3201")
      (footprint "SO8")
      (description "12 BIT A/D CONVERTOR")
      (fields
        (field (name "MANUFACTURER PART NUMBER") "MCP3201-CI/SN")
        (field (name "MANUFACTURER") "Microchip Technology")
      )
      (libsource (lib "Library") (part "MCP3201"))
    )
    (comp (ref "U18")
      (value "HCPL-0600")
      (footprint "SOIC8_50_328_25X90_SMT")
      (description "2.5A Gate Driver Optical Coupling 3750Vrms 1 Channel 8-DIP Gull Wing")
      (fields
        (field (name "MANUFACTURER") "Broadcom Avago")
        (field (name "MANUFACTURER PART NUMBER") "HCPL-3120-500E")
      )
      (libsource (lib "") (part "IC_HCPL-3120-500E_1"))
    )
    (comp (ref "U19")
      (value "HCPL-0600")
      (footprint "SOIC8_50_328_25X90_SMT")
      (description "2.5A Gate Driver Optical Coupling 3750Vrms 1 Channel 8-DIP Gull Wing")
      (fields
        (field (name "MANUFACTURER") "Broadcom Avago")
        (field (name "MANUFACTURER PART NUMBER") "HCPL-3120-500E")
      )
      (libsource (lib "IC") (part "IC_HCPL-3120-500E"))
    )
    (comp (ref "U20")
      (value "HCPL-0600")
      (footprint "SOIC8_50_328_25X90_SMT")
      (description "2.5A Gate Driver Optical Coupling 3750Vrms 1 Channel 8-DIP Gull Wing")
      (fields
        (field (name "MANUFACTURER") "Broadcom Avago")
        (field (name "MANUFACTURER PART NUMBER") "HCPL-3120-500E")
      )
      (libsource (lib "") (part "IC_HCPL-3120-500E_1"))
    )
    (comp (ref "U21")
      (value "B0505S")
      (footprint "B0505S")
      (description "Cắm")
      (libsource (lib "IC") (part "B0505S"))
    )
    (comp (ref "U22")
      (value "MCP3201")
      (footprint "SO8")
      (description "12 BIT A/D CONVERTOR")
      (fields
        (field (name "MANUFACTURER PART NUMBER") "MCP3201-CI/SN")
        (field (name "MANUFACTURER") "Microchip Technology")
      )
      (libsource (lib "Library") (part "MCP3201"))
    )
    (comp (ref "U23")
      (value "HCPL-0600")
      (footprint "SOIC8_50_328_25X90_SMT")
      (description "2.5A Gate Driver Optical Coupling 3750Vrms 1 Channel 8-DIP Gull Wing")
      (fields
        (field (name "MANUFACTURER") "Broadcom Avago")
        (field (name "MANUFACTURER PART NUMBER") "HCPL-3120-500E")
      )
      (libsource (lib "") (part "IC_HCPL-3120-500E_1"))
    )
    (comp (ref "U24")
      (value "HCPL-0600")
      (footprint "SOIC8_50_328_25X90_SMT")
      (description "2.5A Gate Driver Optical Coupling 3750Vrms 1 Channel 8-DIP Gull Wing")
      (fields
        (field (name "MANUFACTURER") "Broadcom Avago")
        (field (name "MANUFACTURER PART NUMBER") "HCPL-3120-500E")
      )
      (libsource (lib "IC") (part "IC_HCPL-3120-500E"))
    )
    (comp (ref "U25")
      (value "HCPL-0600")
      (footprint "SOIC8_50_328_25X90_SMT")
      (description "2.5A Gate Driver Optical Coupling 3750Vrms 1 Channel 8-DIP Gull Wing")
      (fields
        (field (name "MANUFACTURER") "Broadcom Avago")
        (field (name "MANUFACTURER PART NUMBER") "HCPL-3120-500E")
      )
      (libsource (lib "") (part "IC_HCPL-3120-500E_1"))
    )
    (comp (ref "U26")
      (value "B0505S")
      (footprint "B0505S")
      (description "Cắm")
      (libsource (lib "IC") (part "B0505S"))
    )
    (comp (ref "U27")
      (value "MCP3201")
      (footprint "SO8")
      (description "12 BIT A/D CONVERTOR")
      (fields
        (field (name "MANUFACTURER PART NUMBER") "MCP3201-CI/SN")
        (field (name "MANUFACTURER") "Microchip Technology")
      )
      (libsource (lib "Library") (part "MCP3201"))
    )
    (comp (ref "U28")
      (value "HCPL-0600")
      (footprint "SOIC8_50_328_25X90_SMT")
      (description "2.5A Gate Driver Optical Coupling 3750Vrms 1 Channel 8-DIP Gull Wing")
      (fields
        (field (name "MANUFACTURER") "Broadcom Avago")
        (field (name "MANUFACTURER PART NUMBER") "HCPL-3120-500E")
      )
      (libsource (lib "") (part "IC_HCPL-3120-500E_1"))
    )
    (comp (ref "U29")
      (value "HCPL-0600")
      (footprint "SOIC8_50_328_25X90_SMT")
      (description "2.5A Gate Driver Optical Coupling 3750Vrms 1 Channel 8-DIP Gull Wing")
      (fields
        (field (name "MANUFACTURER") "Broadcom Avago")
        (field (name "MANUFACTURER PART NUMBER") "HCPL-3120-500E")
      )
      (libsource (lib "IC") (part "IC_HCPL-3120-500E"))
    )
    (comp (ref "U30")
      (value "HCPL-0600")
      (footprint "SOIC8_50_328_25X90_SMT")
      (description "2.5A Gate Driver Optical Coupling 3750Vrms 1 Channel 8-DIP Gull Wing")
      (fields
        (field (name "MANUFACTURER") "Broadcom Avago")
        (field (name "MANUFACTURER PART NUMBER") "HCPL-3120-500E")
      )
      (libsource (lib "") (part "IC_HCPL-3120-500E_1"))
    )
    (comp (ref "U31")
      (value "B0505S")
      (footprint "B0505S")
      (description "Cắm")
      (libsource (lib "IC") (part "B0505S"))
    )
    (comp (ref "U32")
      (value "MCP3201")
      (footprint "SO8")
      (description "12 BIT A/D CONVERTOR")
      (fields
        (field (name "MANUFACTURER PART NUMBER") "MCP3201-CI/SN")
        (field (name "MANUFACTURER") "Microchip Technology")
      )
      (libsource (lib "Library") (part "MCP3201"))
    )
    (comp (ref "U33")
      (value "HCPL-0600")
      (footprint "SOIC8_50_328_25X90_SMT")
      (description "2.5A Gate Driver Optical Coupling 3750Vrms 1 Channel 8-DIP Gull Wing")
      (fields
        (field (name "MANUFACTURER") "Broadcom Avago")
        (field (name "MANUFACTURER PART NUMBER") "HCPL-3120-500E")
      )
      (libsource (lib "") (part "IC_HCPL-3120-500E_1"))
    )
    (comp (ref "U34")
      (value "HCPL-0600")
      (footprint "SOIC8_50_328_25X90_SMT")
      (description "2.5A Gate Driver Optical Coupling 3750Vrms 1 Channel 8-DIP Gull Wing")
      (fields
        (field (name "MANUFACTURER") "Broadcom Avago")
        (field (name "MANUFACTURER PART NUMBER") "HCPL-3120-500E")
      )
      (libsource (lib "IC") (part "IC_HCPL-3120-500E"))
    )
    (comp (ref "U35")
      (value "HCPL-0600")
      (footprint "SOIC8_50_328_25X90_SMT")
      (description "2.5A Gate Driver Optical Coupling 3750Vrms 1 Channel 8-DIP Gull Wing")
      (fields
        (field (name "MANUFACTURER") "Broadcom Avago")
        (field (name "MANUFACTURER PART NUMBER") "HCPL-3120-500E")
      )
      (libsource (lib "") (part "IC_HCPL-3120-500E_1"))
    )
    (comp (ref "Y1")
      (value "25 MHZ")
      (footprint "Crystal.smd_N")
      (description "Crystal Oscillator")
      (fields (field (name "PUBLISHER") "Altium Limited"))
      (libsource (lib "Miscellaneous Devices") (part "XTAL"))
    )
  )
  (nets
    (net (code "1") (name "/ACT") (class "Default")
      (node (ref "J5") (pin "11") (pinfunction "LED.Y_K_11") (pintype "passive"))
      (node (ref "U14") (pin "7") (pinfunction "ACT_7") (pintype "passive"))
    )
    (net (code "2") (name "/ADC1_CLK") (class "Default")
      (node (ref "R40") (pin "1") (pinfunction "1_1") (pintype "passive"))
      (node (ref "U17") (pin "7") (pinfunction "CLK_7") (pintype "passive"))
      (node (ref "U18") (pin "6") (pinfunction "V0_6") (pintype "passive"))
    )
    (net (code "3") (name "/ADC1_CS") (class "Default")
      (node (ref "R42") (pin "1") (pinfunction "1_1") (pintype "passive"))
      (node (ref "U17") (pin "5") (pinfunction "~{CS}_5") (pintype "passive"))
      (node (ref "U20") (pin "6") (pinfunction "V0_6") (pintype "passive"))
    )
    (net (code "4") (name "/ADC1_DATA") (class "Default")
      (node (ref "U17") (pin "6") (pinfunction "DO_6") (pintype "passive"))
      (node (ref "U19") (pin "3") (pinfunction "CATHODE_3") (pintype "passive"))
    )
    (net (code "5") (name "/ADC2_CLK") (class "Default")
      (node (ref "R48") (pin "1") (pinfunction "1_1") (pintype "passive"))
      (node (ref "U22") (pin "7") (pinfunction "CLK_7") (pintype "passive"))
      (node (ref "U23") (pin "6") (pinfunction "V0_6") (pintype "passive"))
    )
    (net (code "6") (name "/ADC2_CS") (class "Default")
      (node (ref "R50") (pin "1") (pinfunction "1_1") (pintype "passive"))
      (node (ref "U22") (pin "5") (pinfunction "~{CS}_5") (pintype "passive"))
      (node (ref "U25") (pin "6") (pinfunction "V0_6") (pintype "passive"))
    )
    (net (code "7") (name "/ADC2_DATA") (class "Default")
      (node (ref "U22") (pin "6") (pinfunction "DO_6") (pintype "passive"))
      (node (ref "U24") (pin "3") (pinfunction "CATHODE_3") (pintype "passive"))
    )
    (net (code "8") (name "/ADC3_CLK") (class "Default")
      (node (ref "R56") (pin "1") (pinfunction "1_1") (pintype "passive"))
      (node (ref "U27") (pin "7") (pinfunction "CLK_7") (pintype "passive"))
      (node (ref "U28") (pin "6") (pinfunction "V0_6") (pintype "passive"))
    )
    (net (code "9") (name "/ADC3_CS") (class "Default")
      (node (ref "R58") (pin "1") (pinfunction "1_1") (pintype "passive"))
      (node (ref "U27") (pin "5") (pinfunction "~{CS}_5") (pintype "passive"))
      (node (ref "U30") (pin "6") (pinfunction "V0_6") (pintype "passive"))
    )
    (net (code "10") (name "/ADC3_DATA") (class "Default")
      (node (ref "U27") (pin "6") (pinfunction "DO_6") (pintype "passive"))
      (node (ref "U29") (pin "3") (pinfunction "CATHODE_3") (pintype "passive"))
    )
    (net (code "11") (name "/ADC4_CLK") (class "Default")
      (node (ref "R64") (pin "1") (pinfunction "1_1") (pintype "passive"))
      (node (ref "U32") (pin "7") (pinfunction "CLK_7") (pintype "passive"))
      (node (ref "U33") (pin "6") (pinfunction "V0_6") (pintype "passive"))
    )
    (net (code "12") (name "/ADC4_CS") (class "Default")
      (node (ref "R66") (pin "1") (pinfunction "1_1") (pintype "passive"))
      (node (ref "U32") (pin "5") (pinfunction "~{CS}_5") (pintype "passive"))
      (node (ref "U35") (pin "6") (pinfunction "V0_6") (pintype "passive"))
    )
    (net (code "13") (name "/ADC4_DATA") (class "Default")
      (node (ref "U32") (pin "6") (pinfunction "DO_6") (pintype "passive"))
      (node (ref "U34") (pin "3") (pinfunction "CATHODE_3") (pintype "passive"))
    )
    (net (code "14") (name "/CH1_CLK") (class "Default")
      (node (ref "U15") (pin "21") (pinfunction "IO13_21") (pintype "bidirectional"))
      (node (ref "U18") (pin "3") (pinfunction "CATHODE_3") (pintype "passive"))
    )
    (net (code "15") (name "/CH1_CS") (class "Default")
      (node (ref "U15") (pin "23") (pinfunction "IO21_23") (pintype "bidirectional"))
      (node (ref "U20") (pin "3") (pinfunction "CATHODE_3") (pintype "passive"))
    )
    (net (code "16") (name "/CH1_DATA") (class "Default")
      (node (ref "R41") (pin "1") (pinfunction "1_1") (pintype "passive"))
      (node (ref "U15") (pin "22") (pinfunction "IO14_22") (pintype "bidirectional"))
      (node (ref "U19") (pin "6") (pinfunction "V0_6") (pintype "passive"))
    )
    (net (code "17") (name "/CH2_CLK") (class "Default")
      (node (ref "U15") (pin "24") (pinfunction "IO47_24") (pintype "bidirectional"))
      (node (ref "U23") (pin "3") (pinfunction "CATHODE_3") (pintype "passive"))
    )
    (net (code "18") (name "/CH2_CS") (class "Default")
      (node (ref "U15") (pin "26") (pinfunction "IO45_26") (pintype "bidirectional"))
      (node (ref "U25") (pin "3") (pinfunction "CATHODE_3") (pintype "passive"))
    )
    (net (code "19") (name "/CH2_DATA") (class "Default")
      (node (ref "R49") (pin "1") (pinfunction "1_1") (pintype "passive"))
      (node (ref "U15") (pin "25") (pinfunction "IO48_25") (pintype "bidirectional"))
      (node (ref "U24") (pin "6") (pinfunction "V0_6") (pintype "passive"))
    )
    (net (code "20") (name "/CH3_CLK") (class "Default")
      (node (ref "U15") (pin "31") (pinfunction "IO38_31") (pintype "bidirectional"))
      (node (ref "U28") (pin "3") (pinfunction "CATHODE_3") (pintype "passive"))
    )
    (net (code "21") (name "/CH3_CS") (class "Default")
      (node (ref "U15") (pin "33") (pinfunction "IO40_33") (pintype "bidirectional"))
      (node (ref "U30") (pin "3") (pinfunction "CATHODE_3") (pintype "passive"))
    )
    (net (code "22") (name "/CH3_DATA") (class "Default")
      (node (ref "R57") (pin "1") (pinfunction "1_1") (pintype "passive"))
      (node (ref "U15") (pin "32") (pinfunction "IO39_32") (pintype "bidirectional"))
      (node (ref "U29") (pin "6") (pinfunction "V0_6") (pintype "passive"))
    )
    (net (code "23") (name "/CH4_CLK") (class "Default")
      (node (ref "U15") (pin "34") (pinfunction "IO41_34") (pintype "bidirectional"))
      (node (ref "U33") (pin "3") (pinfunction "CATHODE_3") (pintype "passive"))
    )
    (net (code "24") (name "/CH4_CS") (class "Default")
      (node (ref "U15") (pin "38") (pinfunction "IO2_38") (pintype "bidirectional"))
      (node (ref "U35") (pin "3") (pinfunction "CATHODE_3") (pintype "passive"))
    )
    (net (code "25") (name "/CH4_DATA") (class "Default")
      (node (ref "R65") (pin "1") (pinfunction "1_1") (pintype "passive"))
      (node (ref "U15") (pin "35") (pinfunction "IO42_35") (pintype "bidirectional"))
      (node (ref "U34") (pin "6") (pinfunction "V0_6") (pintype "passive"))
    )
    (net (code "26") (name "/D+") (class "Default")
      (node (ref "U15") (pin "14") (pinfunction "IO20_14") (pintype "bidirectional"))
      (node (ref "U2") (pin "4") (pinfunction "I/O2_4") (pintype "bidirectional"))
    )
    (net (code "27") (name "/D-") (class "Default")
      (node (ref "U15") (pin "13") (pinfunction "IO19_13") (pintype "bidirectional"))
      (node (ref "U2") (pin "6") (pinfunction "I/O1_6") (pintype "bidirectional"))
    )
    (net (code "28") (name "/ESP32_CFG2") (class "Default")
      (node (ref "R31") (pin "2") (pinfunction "2_2") (pintype "passive"))
      (node (ref "U14") (pin "11") (pinfunction "CFG_11") (pintype "passive"))
      (node (ref "U15") (pin "10") (pinfunction "IO17_10") (pintype "bidirectional"))
    )
    (net (code "29") (name "/ESP32_EN1") (class "Default")
      (node (ref "U12") (pin "3") (pinfunction "CATHODE_3") (pintype "passive"))
      (node (ref "U15") (pin "7") (pinfunction "IO7_7") (pintype "bidirectional"))
    )
    (net (code "30") (name "/ESP32_RX0") (class "Default")
      (node (ref "R18") (pin "1") (pinfunction "1_1") (pintype "passive"))
      (node (ref "U15") (pin "36") (pinfunction "RXD0_36") (pintype "bidirectional"))
      (node (ref "U8") (pin "6") (pinfunction "V0_6") (pintype "passive"))
    )
    (net (code "31") (name "/ESP32_RX1") (class "Default")
      (node (ref "R26") (pin "1") (pinfunction "1_1") (pintype "passive"))
      (node (ref "U13") (pin "6") (pinfunction "V0_6") (pintype "passive"))
      (node (ref "U15") (pin "6") (pinfunction "IO6_6") (pintype "bidirectional"))
    )
    (net (code "32") (name "/ESP32_RX2") (class "Default")
      (node (ref "U14") (pin "14") (pinfunction "TXD1_14") (pintype "passive"))
      (node (ref "U15") (pin "8") (pinfunction "IO15_8") (pintype "bidirectional"))
    )
    (net (code "33") (name "/ESP32_TX0") (class "Default")
      (node (ref "U15") (pin "37") (pinfunction "TXD0_37") (pintype "bidirectional"))
      (node (ref "U6") (pin "3") (pinfunction "CATHODE_3") (pintype "passive"))
    )
    (net (code "34") (name "/ESP32_TX1") (class "Default")
      (node (ref "U11") (pin "3") (pinfunction "CATHODE_3") (pintype "passive"))
      (node (ref "U15") (pin "5") (pinfunction "IO5_5") (pintype "bidirectional"))
    )
    (net (code "35") (name "/ESP32_TX2") (class "Default")
      (node (ref "U14") (pin "13") (pinfunction "RXD1_13") (pintype "passive"))
      (node (ref "U15") (pin "9") (pinfunction "IO16_9") (pintype "bidirectional"))
    )
    (net (code "36") (name "/LINK{slash}RESET") (class "Default")
      (node (ref "J5") (pin "10") (pinfunction "LED.G_K_10") (pintype "passive"))
      (node (ref "U14") (pin "6") (pinfunction "LINK/RESET_6") (pintype "passive"))
    )
    (net (code "37") (name "/RXN") (class "Default")
      (node (ref "J5") (pin "6") (pinfunction "RD-_6") (pintype "passive"))
      (node (ref "U14") (pin "20") (pinfunction "RXN_20") (pintype "passive"))
    )
    (net (code "38") (name "/RXP") (class "Default")
      (node (ref "J5") (pin "3") (pinfunction "RD+_3") (pintype "passive"))
      (node (ref "U14") (pin "19") (pinfunction "RXP_19") (pintype "passive"))
    )
    (net (code "39") (name "/TXN") (class "Default")
      (node (ref "J5") (pin "2") (pinfunction "TD-_2") (pintype "passive"))
      (node (ref "U14") (pin "2") (pinfunction "TXN_2") (pintype "passive"))
    )
    (net (code "40") (name "/TXP") (class "Default")
      (node (ref "J5") (pin "1") (pinfunction "TD+_1") (pintype "passive"))
      (node (ref "U14") (pin "1") (pinfunction "TXP_1") (pintype "passive"))
    )
    (net (code "41") (name "/UART_EN1") (class "Default")
      (node (ref "R25") (pin "1") (pinfunction "1_1") (pintype "passive"))
      (node (ref "U10") (pin "2") (pinfunction "~{RE}_2") (pintype "passive"))
      (node (ref "U10") (pin "3") (pinfunction "DE_3") (pintype "passive"))
      (node (ref "U12") (pin "6") (pinfunction "V0_6") (pintype "passive"))
    )
    (net (code "42") (name "/UART_RX0") (class "Default")
      (node (ref "D10") (pin "2") (pinfunction "K_2") (pintype "passive"))
      (node (ref "U7") (pin "12") (pinfunction "R1OUT_12") (pintype "output"))
      (node (ref "U8") (pin "3") (pinfunction "CATHODE_3") (pintype "passive"))
    )
    (net (code "43") (name "/UART_RX1") (class "Default")
      (node (ref "D14") (pin "2") (pinfunction "K_2") (pintype "passive"))
      (node (ref "U10") (pin "1") (pinfunction "RO_1") (pintype "passive"))
      (node (ref "U13") (pin "3") (pinfunction "CATHODE_3") (pintype "passive"))
    )
    (net (code "44") (name "/UART_TX0") (class "Default")
      (node (ref "D11") (pin "2") (pinfunction "K_2") (pintype "passive"))
      (node (ref "R14") (pin "1") (pinfunction "1_1") (pintype "passive"))
      (node (ref "U6") (pin "6") (pinfunction "V0_6") (pintype "passive"))
      (node (ref "U7") (pin "11") (pinfunction "T1IN_11") (pintype "input"))
    )
    (net (code "45") (name "/UART_TX1") (class "Default")
      (node (ref "D15") (pin "2") (pinfunction "K_2") (pintype "passive"))
      (node (ref "R24") (pin "1") (pinfunction "1_1") (pintype "passive"))
      (node (ref "U10") (pin "4") (pinfunction "DI_4") (pintype "passive"))
      (node (ref "U11") (pin "6") (pinfunction "V0_6") (pintype "passive"))
    )
    (net (code "46") (name "/USB_D+") (class "Default")
      (node (ref "J2") (pin "A6") (pinfunction "DP1_A6") (pintype "passive"))
      (node (ref "J2") (pin "B6") (pinfunction "DP2_B6") (pintype "passive"))
      (node (ref "U2") (pin "3") (pinfunction "I/O2_3") (pintype "bidirectional"))
    )
    (net (code "47") (name "/USB_D-") (class "Default")
      (node (ref "J2") (pin "A7") (pinfunction "DN1_A7") (pintype "passive"))
      (node (ref "J2") (pin "B7") (pinfunction "DN2_B7") (pintype "passive"))
      (node (ref "U2") (pin "1") (pinfunction "I/O1_1") (pintype "bidirectional"))
    )
    (net (code "48") (name "/XI") (class "Default")
      (node (ref "C29") (pin "1") (pinfunction "1_1") (pintype "passive"))
      (node (ref "U14") (pin "4") (pinfunction "XI_4") (pintype "passive"))
      (node (ref "Y1") (pin "1") (pinfunction "OSC1_1") (pintype "passive"))
    )
    (net (code "49") (name "/XO") (class "Default")
      (node (ref "C31") (pin "1") (pinfunction "1_1") (pintype "passive"))
      (node (ref "U14") (pin "5") (pinfunction "XO_5") (pintype "passive"))
      (node (ref "Y1") (pin "2") (pinfunction "OSC2_2") (pintype "passive"))
    )
    (net (code "50") (name "3.3V") (class "Default")
      (node (ref "C17") (pin "1") (pinfunction "1_1") (pintype "passive"))
      (node (ref "C23") (pin "1") (pinfunction "1_1") (pintype "passive"))
      (node (ref "C24") (pin "2") (pinfunction "2_2") (pintype "passive"))
      (node (ref "C25") (pin "1") (pinfunction "1_1") (pintype "passive"))
      (node (ref "C26") (pin "2") (pinfunction "2_2") (pintype "passive"))
      (node (ref "C32") (pin "1") (pinfunction "1_1") (pintype "passive"))
      (node (ref "C37") (pin "1") (pinfunction "1_1") (pintype "passive"))
      (node (ref "C43") (pin "1") (pinfunction "1_1") (pintype "passive"))
      (node (ref "C49") (pin "1") (pinfunction "1_1") (pintype "passive"))
      (node (ref "C55") (pin "1") (pinfunction "1_1") (pintype "passive"))
      (node (ref "C6") (pin "1") (pinfunction "1_1") (pintype "passive"))
      (node (ref "D19") (pin "1") (pinfunction "A_1") (pintype "passive"))
      (node (ref "D20") (pin "1") (pinfunction "A_1") (pintype "passive"))
      (node (ref "L2") (pin "2") (pinfunction "2_2") (pintype "passive"))
      (node (ref "R10") (pin "2") (pinfunction "2_2") (pintype "passive"))
      (node (ref "R15") (pin "2") (pinfunction "2_2") (pintype "passive"))
      (node (ref "R18") (pin "2") (pinfunction "2_2") (pintype "passive"))
      (node (ref "R26") (pin "2") (pinfunction "2_2") (pintype "passive"))
      (node (ref "R27") (pin "2") (pinfunction "2_2") (pintype "passive"))
      (node (ref "R28") (pin "2") (pinfunction "2_2") (pintype "passive"))
      (node (ref "R30") (pin "2") (pinfunction "2_2") (pintype "passive"))
      (node (ref "R31") (pin "1") (pinfunction "1_1") (pintype "passive"))
      (node (ref "R32") (pin "2") (pinfunction "2_2") (pintype "passive"))
      (node (ref "R33") (pin "2") (pinfunction "2_2") (pintype "passive"))
      (node (ref "R34") (pin "2") (pinfunction "2_2") (pintype "passive"))
      (node (ref "R35") (pin "2") (pinfunction "2_2") (pintype "passive"))
      (node (ref "R41") (pin "2") (pinfunction "2_2") (pintype "passive"))
      (node (ref "R43") (pin "2") (pinfunction "2_2") (pintype "passive"))
      (node (ref "R45") (pin "2") (pinfunction "2_2") (pintype "passive"))
      (node (ref "R49") (pin "2") (pinfunction "2_2") (pintype "passive"))
      (node (ref "R51") (pin "2") (pinfunction "2_2") (pintype "passive"))
      (node (ref "R53") (pin "2") (pinfunction "2_2") (pintype "passive"))
      (node (ref "R57") (pin "2") (pinfunction "2_2") (pintype "passive"))
      (node (ref "R59") (pin "2") (pinfunction "2_2") (pintype "passive"))
      (node (ref "R61") (pin "2") (pinfunction "2_2") (pintype "passive"))
      (node (ref "R65") (pin "2") (pinfunction "2_2") (pintype "passive"))
      (node (ref "R67") (pin "2") (pinfunction "2_2") (pintype "passive"))
      (node (ref "R69") (pin "2") (pinfunction "2_2") (pintype "passive"))
      (node (ref "U13") (pin "7") (pinfunction "V0_7") (pintype "passive"))
      (node (ref "U13") (pin "8") (pinfunction "VCC_8") (pintype "passive"))
      (node (ref "U14") (pin "18") (pinfunction "VCC33_18") (pintype "passive"))
      (node (ref "U14") (pin "3") (pinfunction "VDDK_3") (pintype "passive"))
      (node (ref "U15") (pin "2") (pinfunction "3V3_2") (pintype "power_in"))
      (node (ref "U19") (pin "7") (pinfunction "V0_7") (pintype "passive"))
      (node (ref "U19") (pin "8") (pinfunction "VCC_8") (pintype "passive"))
      (node (ref "U24") (pin "7") (pinfunction "V0_7") (pintype "passive"))
      (node (ref "U24") (pin "8") (pinfunction "VCC_8") (pintype "passive"))
      (node (ref "U29") (pin "7") (pinfunction "V0_7") (pintype "passive"))
      (node (ref "U29") (pin "8") (pinfunction "VCC_8") (pintype "passive"))
      (node (ref "U34") (pin "7") (pinfunction "V0_7") (pintype "passive"))
      (node (ref "U34") (pin "8") (pinfunction "VCC_8") (pintype "passive"))
      (node (ref "U8") (pin "7") (pinfunction "V0_7") (pintype "passive"))
      (node (ref "U8") (pin "8") (pinfunction "VCC_8") (pintype "passive"))
    )
    (net (code "51") (name "5V") (class "Default")
      (node (ref "C34") (pin "1") (pinfunction "1_1") (pintype "passive"))
      (node (ref "C40") (pin "1") (pinfunction "1_1") (pintype "passive"))
      (node (ref "C46") (pin "1") (pinfunction "1_1") (pintype "passive"))
      (node (ref "C4_") (pin "1") (pinfunction "1_1") (pintype "passive"))
      (node (ref "C52") (pin "1") (pinfunction "1_1") (pintype "passive"))
      (node (ref "D7") (pin "2") (pinfunction "K_2") (pintype "passive"))
      (node (ref "D8") (pin "1") (pinfunction "A_1") (pintype "passive"))
      (node (ref "Q1") (pin "3") (pinfunction "S_3") (pintype "passive"))
      (node (ref "R6") (pin "2") (pinfunction "2_2") (pintype "passive"))
      (node (ref "U16") (pin "2") (pinfunction "Vin_2") (pintype "passive"))
      (node (ref "U21") (pin "2") (pinfunction "Vin_2") (pintype "passive"))
      (node (ref "U26") (pin "2") (pinfunction "Vin_2") (pintype "passive"))
      (node (ref "U3") (pin "7") (pinfunction "VIN_7") (pintype "power_in"))
      (node (ref "U31") (pin "2") (pinfunction "Vin_2") (pintype "passive"))
      (node (ref "U4") (pin "6") (pinfunction "SENSE_6") (pintype "input"))
    )
    (net (code "52") (name "5VP") (class "Default")
      (node (ref "C19") (pin "1") (pinfunction "1_1") (pintype "passive"))
      (node (ref "C2") (pin "1") (pinfunction "1_1") (pintype "passive"))
      (node (ref "C8") (pin "1") (pinfunction "1_1") (pintype "passive"))
      (node (ref "D3") (pin "1") (pinfunction "A_1") (pintype "passive"))
      (node (ref "L1") (pin "2") (pinfunction "2_2") (pintype "passive"))
      (node (ref "Q1") (pin "2") (pinfunction "D_2") (pintype "passive"))
      (node (ref "U1") (pin "4") (pinfunction "FB_4") (pintype "input"))
      (node (ref "U4") (pin "1") (pinfunction "VIN_1") (pintype "input"))
      (node (ref "U5") (pin "2") (pinfunction "Vin_2") (pintype "passive"))
      (node (ref "U9") (pin "2") (pinfunction "Vin_2") (pintype "passive"))
    )
    (net (code "53") (name "5V_RS232") (class "Default")
      (node (ref "C10") (pin "2") (pinfunction "2_2") (pintype "passive"))
      (node (ref "C14") (pin "2") (pinfunction "2_2") (pintype "passive"))
      (node (ref "C15") (pin "2") (pinfunction "2_2") (pintype "passive"))
      (node (ref "C9") (pin "2") (pinfunction "2_2") (pintype "passive"))
      (node (ref "R12") (pin "2") (pinfunction "2_2") (pintype "passive"))
      (node (ref "R13") (pin "2") (pinfunction "2_2") (pintype "passive"))
      (node (ref "R14") (pin "2") (pinfunction "2_2") (pintype "passive"))
      (node (ref "R19") (pin "1") (pinfunction "1_1") (pintype "passive"))
      (node (ref "U5") (pin "4") (pinfunction "Vout_4") (pintype "passive"))
      (node (ref "U6") (pin "7") (pinfunction "V0_7") (pintype "passive"))
      (node (ref "U6") (pin "8") (pinfunction "VCC_8") (pintype "passive"))
      (node (ref "U7") (pin "16") (pinfunction "VCC_16") (pintype "power_in"))
    )
    (net (code "54") (name "5V_RS485") (class "Default")
      (node (ref "C18") (pin "2") (pinfunction "2_2") (pintype "passive"))
      (node (ref "C20") (pin "2") (pinfunction "2_2") (pintype "passive"))
      (node (ref "C21") (pin "2") (pinfunction "2_2") (pintype "passive"))
      (node (ref "C22") (pin "2") (pinfunction "2_2") (pintype "passive"))
      (node (ref "R20") (pin "2") (pinfunction "2_2") (pintype "passive"))
      (node (ref "R21") (pin "2") (pinfunction "2_2") (pintype "passive"))
      (node (ref "R24") (pin "2") (pinfunction "2_2") (pintype "passive"))
      (node (ref "R25") (pin "2") (pinfunction "2_2") (pintype "passive"))
      (node (ref "R29") (pin "1") (pinfunction "1_1") (pintype "passive"))
      (node (ref "U10") (pin "8") (pinfunction "VCC_8") (pintype "passive"))
      (node (ref "U11") (pin "7") (pinfunction "V0_7") (pintype "passive"))
      (node (ref "U11") (pin "8") (pinfunction "VCC_8") (pintype "passive"))
      (node (ref "U12") (pin "7") (pinfunction "V0_7") (pintype "passive"))
      (node (ref "U12") (pin "8") (pinfunction "VCC_8") (pintype "passive"))
      (node (ref "U9") (pin "4") (pinfunction "Vout_4") (pintype "passive"))
    )
    (net (code "55") (name "24V") (class "Default")
      (node (ref "C1") (pin "1") (pinfunction "1_1") (pintype "passive"))
      (node (ref "D1") (pin "2") (pinfunction "K_2") (pintype "passive"))
      (node (ref "D2") (pin "1") (pinfunction "A_1") (pintype "passive"))
      (node (ref "D5") (pin "1") (pinfunction "A_1") (pintype "passive"))
      (node (ref "U1") (pin "1") (pinfunction "VIN_1") (pintype "power_in"))
    )
    (net (code "56") (name "GND") (class "Default")
      (node (ref "C1") (pin "2") (pinfunction "2_2") (pintype "passive"))
      (node (ref "C17") (pin "2") (pinfunction "2_2") (pintype "passive"))
      (node (ref "C19") (pin "2") (pinfunction "2_2") (pintype "passive"))
      (node (ref "C2") (pin "2") (pinfunction "2_2") (pintype "passive"))
      (node (ref "C23") (pin "2") (pinfunction "2_2") (pintype "passive"))
      (node (ref "C24") (pin "1") (pinfunction "1_1") (pintype "passive"))
      (node (ref "C25") (pin "2") (pinfunction "2_2") (pintype "passive"))
      (node (ref "C26") (pin "1") (pinfunction "1_1") (pintype "passive"))
      (node (ref "C27") (pin "1") (pinfunction "1_1") (pintype "passive"))
      (node (ref "C28") (pin "1") (pinfunction "1_1") (pintype "passive"))
      (node (ref "C29") (pin "2") (pinfunction "2_2") (pintype "passive"))
      (node (ref "C30") (pin "1") (pinfunction "1_1") (pintype "passive"))
      (node (ref "C31") (pin "2") (pinfunction "2_2") (pintype "passive"))
      (node (ref "C32") (pin "2") (pinfunction "2_2") (pintype "passive"))
      (node (ref "C34") (pin "2") (pinfunction "2_2") (pintype "passive"))
      (node (ref "C37") (pin "2") (pinfunction "2_2") (pintype "passive"))
      (node (ref "C40") (pin "2") (pinfunction "2_2") (pintype "passive"))
      (node (ref "C43") (pin "2") (pinfunction "2_2") (pintype "passive"))
      (node (ref "C46") (pin "2") (pinfunction "2_2") (pintype "passive"))
      (node (ref "C49") (pin "2") (pinfunction "2_2") (pintype "passive"))
      (node (ref "C4_") (pin "2") (pinfunction "2_2") (pintype "passive"))
      (node (ref "C52") (pin "2") (pinfunction "2_2") (pintype "passive"))
      (node (ref "C55") (pin "2") (pinfunction "2_2") (pintype "passive"))
      (node (ref "C6") (pin "2") (pinfunction "2_2") (pintype "passive"))
      (node (ref "C7") (pin "1") (pinfunction "1_1") (pintype "passive"))
      (node (ref "C8") (pin "2") (pinfunction "2_2") (pintype "passive"))
      (node (ref "D5") (pin "2") (pinfunction "K_2") (pintype "passive"))
      (node (ref "D6") (pin "1") (pinfunction "A_1") (pintype "passive"))
      (node (ref "D9") (pin "1") (pinfunction "A_1") (pintype "passive"))
      (node (ref "J1") (pin "2") (pinfunction "2_2") (pintype "passive"))
      (node (ref "J2") (pin "A1_B12") (pinfunction "GND_A1_B12") (pintype "power_in"))
      (node (ref "J2") (pin "B1_A12") (pinfunction "GND_B1_A12") (pintype "power_in"))
      (node (ref "J5") (pin "8") (pinfunction "CHS_GND_8") (pintype "passive"))
      (node (ref "R1") (pin "1") (pinfunction "1_1") (pintype "passive"))
      (node (ref "R11") (pin "1") (pinfunction "1_1") (pintype "passive"))
      (node (ref "R2") (pin "1") (pinfunction "1_1") (pintype "passive"))
      (node (ref "R3") (pin "1") (pinfunction "1_1") (pintype "passive"))
      (node (ref "R4") (pin "2") (pinfunction "2_2") (pintype "passive"))
      (node (ref "R5") (pin "2") (pinfunction "2_2") (pintype "passive"))
      (node (ref "R8") (pin "2") (pinfunction "2_2") (pintype "passive"))
      (node (ref "R9") (pin "1") (pinfunction "1_1") (pintype "passive"))
      (node (ref "SW1") (pin "1") (pinfunction "1_1") (pintype "passive"))
      (node (ref "SW2") (pin "2") (pinfunction "2_2") (pintype "passive"))
      (node (ref "U1") (pin "3") (pinfunction "GND_3") (pintype "power_in"))
      (node (ref "U1") (pin "5") (pinfunction "~{ON}/OFF_5") (pintype "input"))
      (node (ref "U13") (pin "5") (pinfunction "VEE_5") (pintype "passive"))
      (node (ref "U14") (pin "17") (pinfunction "GND_17") (pintype "passive"))
      (node (ref "U15") (pin "1") (pinfunction "GND_1") (pintype "power_in"))
      (node (ref "U15") (pin "40") (pinfunction "GND_40") (pintype "power_in"))
      (node (ref "U15") (pin "41") (pinfunction "GND_41") (pintype "power_in"))
      (node (ref "U15") (pin "42") (pinfunction "GND_42") (pintype "power_in"))
      (node (ref "U15") (pin "43") (pinfunction "GND_43") (pintype "power_in"))
      (node (ref "U15") (pin "44") (pinfunction "GND_44") (pintype "power_in"))
      (node (ref "U15") (pin "45") (pinfunction "GND_45") (pintype "power_in"))
      (node (ref "U15") (pin "46") (pinfunction "GND_46") (pintype "power_in"))
      (node (ref "U15") (pin "47") (pinfunction "GND_47") (pintype "power_in"))
      (node (ref "U15") (pin "48") (pinfunction "GND_48") (pintype "power_in"))
      (node (ref "U15") (pin "49") (pinfunction "GND_49") (pintype "power_in"))
      (node (ref "U16") (pin "1") (pinfunction "GND_1") (pintype "passive"))
      (node (ref "U19") (pin "5") (pinfunction "VEE_5") (pintype "passive"))
      (node (ref "U2") (pin "2") (pinfunction "GND_2") (pintype "power_in"))
      (node (ref "U21") (pin "1") (pinfunction "GND_1") (pintype "passive"))
      (node (ref "U24") (pin "5") (pinfunction "VEE_5") (pintype "passive"))
      (node (ref "U26") (pin "1") (pinfunction "GND_1") (pintype "passive"))
      (node (ref "U29") (pin "5") (pinfunction "VEE_5") (pintype "passive"))
      (node (ref "U3") (pin "5") (pinfunction "GND_5") (pintype "power_in"))
      (node (ref "U31") (pin "1") (pinfunction "GND_1") (pintype "passive"))
      (node (ref "U34") (pin "5") (pinfunction "VEE_5") (pintype "passive"))
      (node (ref "U4") (pin "3") (pinfunction "CTL_3") (pintype "input"))
      (node (ref "U5") (pin "1") (pinfunction "GND_1") (pintype "passive"))
      (node (ref "U8") (pin "5") (pinfunction "VEE_5") (pintype "passive"))
      (node (ref "U9") (pin "1") (pinfunction "GND_1") (pintype "passive"))
    )
    (net (code "57") (name "GND1") (class "Default")
      (node (ref "C33") (pin "1") (pinfunction "1_1") (pintype "passive"))
      (node (ref "C35") (pin "2") (pinfunction "2_2") (pintype "passive"))
      (node (ref "C36") (pin "1") (pinfunction "1_1") (pintype "passive"))
      (node (ref "C38") (pin "1") (pinfunction "1_1") (pintype "passive"))
      (node (ref "J6") (pin "3") (pinfunction "3_3") (pintype "passive"))
      (node (ref "R39") (pin "1") (pinfunction "1_1") (pintype "passive"))
      (node (ref "U16") (pin "3") (pinfunction "0V_3") (pintype "passive"))
      (node (ref "U17") (pin "3") (pintype "passive"))
      (node (ref "U17") (pin "4") (pinfunction "VSS_4") (pintype "passive"))
      (node (ref "U18") (pin "5") (pinfunction "VEE_5") (pintype "passive"))
      (node (ref "U19") (pin "4") (pinfunction "NC_4") (pintype "passive"))
      (node (ref "U20") (pin "5") (pinfunction "VEE_5") (pintype "passive"))
    )
    (net (code "58") (name "GND2") (class "Default")
      (node (ref "C39") (pin "1") (pinfunction "1_1") (pintype "passive"))
      (node (ref "C41") (pin "2") (pinfunction "2_2") (pintype "passive"))
      (node (ref "C42") (pin "1") (pinfunction "1_1") (pintype "passive"))
      (node (ref "C44") (pin "1") (pinfunction "1_1") (pintype "passive"))
      (node (ref "J7") (pin "3") (pinfunction "3_3") (pintype "passive"))
      (node (ref "R47") (pin "1") (pinfunction "1_1") (pintype "passive"))
      (node (ref "U21") (pin "3") (pinfunction "0V_3") (pintype "passive"))
      (node (ref "U22") (pin "3") (pintype "passive"))
      (node (ref "U22") (pin "4") (pinfunction "VSS_4") (pintype "passive"))
      (node (ref "U23") (pin "5") (pinfunction "VEE_5") (pintype "passive"))
      (node (ref "U24") (pin "4") (pinfunction "NC_4") (pintype "passive"))
      (node (ref "U25") (pin "5") (pinfunction "VEE_5") (pintype "passive"))
    )
    (net (code "59") (name "GND3") (class "Default")
      (node (ref "C45") (pin "1") (pinfunction "1_1") (pintype "passive"))
      (node (ref "C47") (pin "2") (pinfunction "2_2") (pintype "passive"))
      (node (ref "C48") (pin "1") (pinfunction "1_1") (pintype "passive"))
      (node (ref "C50") (pin "1") (pinfunction "1_1") (pintype "passive"))
      (node (ref "J8") (pin "3") (pinfunction "3_3") (pintype "passive"))
      (node (ref "R55") (pin "1") (pinfunction "1_1") (pintype "passive"))
      (node (ref "U26") (pin "3") (pinfunction "0V_3") (pintype "passive"))
      (node (ref "U27") (pin "3") (pintype "passive"))
      (node (ref "U27") (pin "4") (pinfunction "VSS_4") (pintype "passive"))
      (node (ref "U28") (pin "5") (pinfunction "VEE_5") (pintype "passive"))
      (node (ref "U29") (pin "4") (pinfunction "NC_4") (pintype "passive"))
      (node (ref "U30") (pin "5") (pinfunction "VEE_5") (pintype "passive"))
    )
    (net (code "60") (name "GND4") (class "Default")
      (node (ref "C51") (pin "1") (pinfunction "1_1") (pintype "passive"))
      (node (ref "C53") (pin "2") (pinfunction "2_2") (pintype "passive"))
      (node (ref "C54") (pin "1") (pinfunction "1_1") (pintype "passive"))
      (node (ref "C56") (pin "1") (pinfunction "1_1") (pintype "passive"))
      (node (ref "J9") (pin "3") (pinfunction "3_3") (pintype "passive"))
      (node (ref "R63") (pin "1") (pinfunction "1_1") (pintype "passive"))
      (node (ref "U31") (pin "3") (pinfunction "0V_3") (pintype "passive"))
      (node (ref "U32") (pin "3") (pintype "passive"))
      (node (ref "U32") (pin "4") (pinfunction "VSS_4") (pintype "passive"))
      (node (ref "U33") (pin "5") (pinfunction "VEE_5") (pintype "passive"))
      (node (ref "U35") (pin "5") (pinfunction "VEE_5") (pintype "passive"))
    )
    (net (code "61") (name "GND_RS232") (class "Default")
      (node (ref "C10") (pin "1") (pinfunction "1_1") (pintype "passive"))
      (node (ref "C11") (pin "2") (pinfunction "2_2") (pintype "passive"))
      (node (ref "C14") (pin "1") (pinfunction "1_1") (pintype "passive"))
      (node (ref "C16") (pin "1") (pinfunction "1_1") (pintype "passive"))
      (node (ref "C9") (pin "1") (pinfunction "1_1") (pintype "passive"))
      (node (ref "D12") (pin "2") (pinfunction "K_2") (pintype "passive"))
      (node (ref "D13") (pin "2") (pinfunction "K_2") (pintype "passive"))
      (node (ref "J3") (pin "5") (pinfunction "5_5") (pintype "passive"))
      (node (ref "U5") (pin "3") (pinfunction "0V_3") (pintype "passive"))
      (node (ref "U6") (pin "5") (pinfunction "VEE_5") (pintype "passive"))
      (node (ref "U7") (pin "15") (pinfunction "GND_15") (pintype "power_in"))
    )
    (net (code "62") (name "GND_RS485") (class "Default")
      (node (ref "C18") (pin "1") (pinfunction "1_1") (pintype "passive"))
      (node (ref "C20") (pin "1") (pinfunction "1_1") (pintype "passive"))
      (node (ref "C21") (pin "1") (pinfunction "1_1") (pintype "passive"))
      (node (ref "C22") (pin "1") (pinfunction "1_1") (pintype "passive"))
      (node (ref "D16") (pin "1") (pinfunction "A_1") (pintype "passive"))
      (node (ref "D18") (pin "2") (pinfunction "K_2") (pintype "passive"))
      (node (ref "J4") (pin "3") (pinfunction "3_3") (pintype "passive"))
      (node (ref "U10") (pin "5") (pinfunction "GND_5") (pintype "passive"))
      (node (ref "U11") (pin "5") (pinfunction "VEE_5") (pintype "passive"))
      (node (ref "U12") (pin "5") (pinfunction "VEE_5") (pintype "passive"))
      (node (ref "U9") (pin "3") (pinfunction "0V_3") (pintype "passive"))
    )
    (net (code "63") (name "Net-(C5-Pad2)") (class "Default")
      (node (ref "C5") (pin "2") (pinfunction "2_2") (pintype "passive"))
      (node (ref "R9") (pin "2") (pinfunction "2_2") (pintype "passive"))
    )
    (net (code "64") (name "Net-(C7-Pad2)") (class "Default")
      (node (ref "C7") (pin "2") (pinfunction "2_2") (pintype "passive"))
      (node (ref "J2") (pin "SH1") (pinfunction "SHIELD_SH1") (pintype "passive"))
      (node (ref "J2") (pin "SH2") (pinfunction "SHIELD_SH2") (pintype "passive"))
      (node (ref "J2") (pin "SH3") (pinfunction "SHIELD_SH3") (pintype "passive"))
      (node (ref "J2") (pin "SH4") (pinfunction "SHIELD_SH4") (pintype "passive"))
    )
    (net (code "65") (name "Net-(C30-Pad2)") (class "Default")
      (node (ref "C30") (pin "2") (pinfunction "2_2") (pintype "passive"))
      (node (ref "J5") (pin "13") (pinfunction "SHIELD_13") (pintype "passive"))
      (node (ref "J5") (pin "14") (pinfunction "SHIELD_14") (pintype "passive"))
    )
    (net (code "66") (name "Net-(D1-A)") (class "Default")
      (node (ref "D1") (pin "1") (pinfunction "A_1") (pintype "passive"))
      (node (ref "F1") (pin "2") (pinfunction "2_2") (pintype "passive"))
    )
    (net (code "67") (name "Net-(D2-K)") (class "Default")
      (node (ref "D2") (pin "2") (pinfunction "K_2") (pintype "passive"))
      (node (ref "R1") (pin "2") (pinfunction "2_2") (pintype "passive"))
    )
    (net (code "68") (name "Net-(D3-K)") (class "Default")
      (node (ref "D3") (pin "2") (pinfunction "K_2") (pintype "passive"))
      (node (ref "R2") (pin "2") (pinfunction "2_2") (pintype "passive"))
    )
    (net (code "69") (name "Net-(D4-K)") (class "Default")
      (node (ref "D4") (pin "2") (pinfunction "K_2") (pintype "passive"))
      (node (ref "R3") (pin "2") (pinfunction "2_2") (pintype "passive"))
    )
    (net (code "70") (name "Net-(D6-K)") (class "Default")
      (node (ref "D6") (pin "2") (pinfunction "K_2") (pintype "passive"))
      (node (ref "L1") (pin "1") (pinfunction "1_1") (pintype "passive"))
      (node (ref "U1") (pin "2") (pinfunction "OUT_2") (pintype "power_in"))
    )
    (net (code "71") (name "Net-(D8-K)") (class "Default")
      (node (ref "D8") (pin "2") (pinfunction "K_2") (pintype "passive"))
      (node (ref "R7") (pin "2") (pinfunction "2_2") (pintype "passive"))
    )
    (net (code "72") (name "Net-(D9-K)") (class "Default")
      (node (ref "C3") (pin "2") (pinfunction "2_2") (pintype "passive"))
      (node (ref "D9") (pin "2") (pinfunction "K_2") (pintype "passive"))
      (node (ref "L2") (pin "1") (pinfunction "1_1") (pintype "passive"))
      (node (ref "U3") (pin "1") (pinfunction "SW_1") (pintype "output"))
    )
    (net (code "73") (name "Net-(D10-A)") (class "Default")
      (node (ref "D10") (pin "1") (pinfunction "A_1") (pintype "passive"))
      (node (ref "R12") (pin "1") (pinfunction "1_1") (pintype "passive"))
    )
    (net (code "74") (name "Net-(D11-A)") (class "Default")
      (node (ref "D11") (pin "1") (pinfunction "A_1") (pintype "passive"))
      (node (ref "R13") (pin "1") (pinfunction "1_1") (pintype "passive"))
    )
    (net (code "75") (name "Net-(D12-A)") (class "Default")
      (node (ref "D12") (pin "1") (pinfunction "A_1") (pintype "passive"))
      (node (ref "J3") (pin "2") (pinfunction "2_2") (pintype "passive"))
      (node (ref "R16") (pin "1") (pinfunction "1_1") (pintype "passive"))
    )
    (net (code "76") (name "Net-(D13-A)") (class "Default")
      (node (ref "D13") (pin "1") (pinfunction "A_1") (pintype "passive"))
      (node (ref "J3") (pin "3") (pinfunction "3_3") (pintype "passive"))
      (node (ref "R17") (pin "1") (pinfunction "1_1") (pintype "passive"))
    )
    (net (code "77") (name "Net-(D14-A)") (class "Default")
      (node (ref "D14") (pin "1") (pinfunction "A_1") (pintype "passive"))
      (node (ref "R20") (pin "1") (pinfunction "1_1") (pintype "passive"))
    )
    (net (code "78") (name "Net-(D15-A)") (class "Default")
      (node (ref "D15") (pin "1") (pinfunction "A_1") (pintype "passive"))
      (node (ref "R21") (pin "1") (pinfunction "1_1") (pintype "passive"))
    )
    (net (code "79") (name "Net-(D16-K)") (class "Default")
      (node (ref "D16") (pin "2") (pinfunction "K_2") (pintype "passive"))
      (node (ref "D17") (pin "1") (pinfunction "A_1") (pintype "passive"))
      (node (ref "J4") (pin "1") (pinfunction "1_1") (pintype "passive"))
      (node (ref "R22") (pin "1") (pinfunction "1_1") (pintype "passive"))
    )
    (net (code "80") (name "Net-(D17-K)") (class "Default")
      (node (ref "D17") (pin "2") (pinfunction "K_2") (pintype "passive"))
      (node (ref "D18") (pin "1") (pinfunction "A_1") (pintype "passive"))
      (node (ref "J4") (pin "2") (pinfunction "2_2") (pintype "passive"))
      (node (ref "R23") (pin "1") (pinfunction "1_1") (pintype "passive"))
    )
    (net (code "81") (name "Net-(D19-K)") (class "Default")
      (node (ref "D19") (pin "2") (pinfunction "K_2") (pintype "passive"))
      (node (ref "R36") (pin "1") (pinfunction "1_1") (pintype "passive"))
    )
    (net (code "82") (name "Net-(D20-K)") (class "Default")
      (node (ref "D20") (pin "2") (pinfunction "K_2") (pintype "passive"))
      (node (ref "R37") (pin "1") (pinfunction "1_1") (pintype "passive"))
    )
    (net (code "83") (name "Net-(F1-Pad1)") (class "Default")
      (node (ref "F1") (pin "1") (pinfunction "1_1") (pintype "passive"))
      (node (ref "J1") (pin "1") (pinfunction "1_1") (pintype "passive"))
    )
    (net (code "84") (name "Net-(J2-CC1)") (class "Default")
      (node (ref "J2") (pin "A5") (pinfunction "CC1_A5") (pintype "passive"))
      (node (ref "R5") (pin "1") (pinfunction "1_1") (pintype "passive"))
    )
    (net (code "85") (name "Net-(J2-CC2)") (class "Default")
      (node (ref "J2") (pin "B5") (pinfunction "CC2_B5") (pintype "passive"))
      (node (ref "R4") (pin "1") (pinfunction "1_1") (pintype "passive"))
    )
    (net (code "86") (name "Net-(J3-MH1)") (class "Default")
      (node (ref "C11") (pin "1") (pinfunction "1_1") (pintype "passive"))
      (node (ref "J3") (pin "10") (pinfunction "MH1_10") (pintype "passive"))
      (node (ref "J3") (pin "11") (pinfunction "MH2_11") (pintype "passive"))
    )
    (net (code "87") (name "Net-(J5-LED.G_A)") (class "Default")
      (node (ref "J5") (pin "9") (pinfunction "LED.G_A_9") (pintype "passive"))
      (node (ref "R33") (pin "1") (pinfunction "1_1") (pintype "passive"))
    )
    (net (code "88") (name "Net-(J5-LED.Y_A)") (class "Default")
      (node (ref "J5") (pin "12") (pinfunction "LED.Y_A_12") (pintype "passive"))
      (node (ref "R32") (pin "1") (pinfunction "1_1") (pintype "passive"))
    )
    (net (code "89") (name "Net-(J5-RCT)") (class "Default")
      (node (ref "C28") (pin "2") (pinfunction "2_2") (pintype "passive"))
      (node (ref "J5") (pin "5") (pinfunction "RCT_5") (pintype "passive"))
    )
    (net (code "90") (name "Net-(J5-TCT)") (class "Default")
      (node (ref "C27") (pin "2") (pinfunction "2_2") (pintype "passive"))
      (node (ref "J5") (pin "4") (pinfunction "TCT_4") (pintype "passive"))
    )
    (net (code "91") (name "Net-(J6-Pad1)") (class "Default")
      (node (ref "J6") (pin "1") (pinfunction "1_1") (pintype "passive"))
      (node (ref "R38") (pin "1") (pinfunction "1_1") (pintype "passive"))
      (node (ref "R39") (pin "2") (pinfunction "2_2") (pintype "passive"))
    )
    (net (code "92") (name "Net-(J6-Pad2)") (class "Default")
      (node (ref "J6") (pin "2") (pinfunction "2_2") (pintype "passive"))
      (node (ref "U17") (pin "2") (pintype "passive"))
    )
    (net (code "93") (name "Net-(J7-Pad1)") (class "Default")
      (node (ref "J7") (pin "1") (pinfunction "1_1") (pintype "passive"))
      (node (ref "R46") (pin "1") (pinfunction "1_1") (pintype "passive"))
      (node (ref "R47") (pin "2") (pinfunction "2_2") (pintype "passive"))
    )
    (net (code "94") (name "Net-(J7-Pad2)") (class "Default")
      (node (ref "J7") (pin "2") (pinfunction "2_2") (pintype "passive"))
      (node (ref "U22") (pin "2") (pintype "passive"))
    )
    (net (code "95") (name "Net-(J8-Pad1)") (class "Default")
      (node (ref "J8") (pin "1") (pinfunction "1_1") (pintype "passive"))
      (node (ref "R54") (pin "1") (pinfunction "1_1") (pintype "passive"))
      (node (ref "R55") (pin "2") (pinfunction "2_2") (pintype "passive"))
    )
    (net (code "96") (name "Net-(J8-Pad2)") (class "Default")
      (node (ref "J8") (pin "2") (pinfunction "2_2") (pintype "passive"))
      (node (ref "U27") (pin "2") (pintype "passive"))
    )
    (net (code "97") (name "Net-(J9-Pad1)") (class "Default")
      (node (ref "J9") (pin "1") (pinfunction "1_1") (pintype "passive"))
      (node (ref "R62") (pin "1") (pinfunction "1_1") (pintype "passive"))
      (node (ref "R63") (pin "2") (pinfunction "2_2") (pintype "passive"))
    )
    (net (code "98") (name "Net-(J9-Pad2)") (class "Default")
      (node (ref "J9") (pin "2") (pinfunction "2_2") (pintype "passive"))
      (node (ref "U32") (pin "2") (pintype "passive"))
    )
    (net (code "99") (name "Net-(Q1-G)") (class "Default")
      (node (ref "Q1") (pin "1") (pinfunction "G_1") (pintype "passive"))
      (node (ref "U4") (pin "5") (pinfunction "GATE_5") (pintype "passive"))
    )
    (net (code "100") (name "Net-(U3-BST)") (class "Default")
      (node (ref "C3") (pin "1") (pinfunction "1_1") (pintype "passive"))
      (node (ref "U3") (pin "8") (pinfunction "BST_8") (pintype "passive"))
    )
    (net (code "101") (name "Net-(U3-COMP)") (class "Default")
      (node (ref "C5") (pin "1") (pinfunction "1_1") (pintype "passive"))
      (node (ref "U3") (pin "3") (pinfunction "COMP_3") (pintype "output"))
    )
    (net (code "102") (name "Net-(U3-EN)") (class "Default")
      (node (ref "R6") (pin "1") (pinfunction "1_1") (pintype "passive"))
      (node (ref "U3") (pin "2") (pinfunction "EN_2") (pintype "input"))
    )
    (net (code "103") (name "Net-(U3-FB)") (class "Default")
      (node (ref "R10") (pin "1") (pinfunction "1_1") (pintype "passive"))
      (node (ref "R11") (pin "2") (pinfunction "2_2") (pintype "passive"))
      (node (ref "U3") (pin "4") (pinfunction "FB_4") (pintype "input"))
    )
    (net (code "104") (name "Net-(U3-FREQ)") (class "Default")
      (node (ref "R8") (pin "1") (pinfunction "1_1") (pintype "passive"))
      (node (ref "U3") (pin "6") (pinfunction "FREQ_6") (pintype "input"))
    )
    (net (code "105") (name "Net-(U4-STAT)") (class "Default")
      (node (ref "R7") (pin "1") (pinfunction "1_1") (pintype "passive"))
      (node (ref "U4") (pin "4") (pinfunction "STAT_4") (pintype "output"))
    )
    (net (code "106") (name "Net-(U6-ANODE)") (class "Default")
      (node (ref "R15") (pin "1") (pinfunction "1_1") (pintype "passive"))
      (node (ref "U6") (pin "2") (pinfunction "ANODE_2") (pintype "passive"))
    )
    (net (code "107") (name "Net-(U7-C+)") (class "Default")
      (node (ref "C12") (pin "2") (pinfunction "2_2") (pintype "passive"))
      (node (ref "U7") (pin "1") (pinfunction "C+_1") (pintype "passive"))
    )
    (net (code "108") (name "Net-(U7-C1-)") (class "Default")
      (node (ref "C12") (pin "1") (pinfunction "1_1") (pintype "passive"))
      (node (ref "U7") (pin "3") (pinfunction "C1-_3") (pintype "passive"))
    )
    (net (code "109") (name "Net-(U7-C2+)") (class "Default")
      (node (ref "C13") (pin "1") (pinfunction "1_1") (pintype "passive"))
      (node (ref "U7") (pin "4") (pinfunction "C2+_4") (pintype "passive"))
    )
    (net (code "110") (name "Net-(U7-C2-)") (class "Default")
      (node (ref "C13") (pin "2") (pinfunction "2_2") (pintype "passive"))
      (node (ref "U7") (pin "5") (pinfunction "C2-_5") (pintype "passive"))
    )
    (net (code "111") (name "Net-(U7-R1IN)") (class "Default")
      (node (ref "R17") (pin "2") (pinfunction "2_2") (pintype "passive"))
      (node (ref "U7") (pin "13") (pinfunction "R1IN_13") (pintype "input"))
    )
    (net (code "112") (name "Net-(U7-T1OUT)") (class "Default")
      (node (ref "R16") (pin "2") (pinfunction "2_2") (pintype "passive"))
      (node (ref "U7") (pin "14") (pinfunction "T1OUT_14") (pintype "output"))
    )
    (net (code "113") (name "Net-(U7-V+)") (class "Default")
      (node (ref "C15") (pin "1") (pinfunction "1_1") (pintype "passive"))
      (node (ref "U7") (pin "2") (pinfunction "V+_2") (pintype "passive"))
    )
    (net (code "114") (name "Net-(U7-V-)") (class "Default")
      (node (ref "C16") (pin "2") (pinfunction "2_2") (pintype "passive"))
      (node (ref "U7") (pin "6") (pinfunction "V-_6") (pintype "passive"))
    )
    (net (code "115") (name "Net-(U8-ANODE)") (class "Default")
      (node (ref "R19") (pin "2") (pinfunction "2_2") (pintype "passive"))
      (node (ref "U8") (pin "2") (pinfunction "ANODE_2") (pintype "passive"))
    )
    (net (code "116") (name "Net-(U10-A)") (class "Default")
      (node (ref "R23") (pin "2") (pinfunction "2_2") (pintype "passive"))
      (node (ref "U10") (pin "6") (pinfunction "A_6") (pintype "passive"))
    )
    (net (code "117") (name "Net-(U10-B)") (class "Default")
      (node (ref "R22") (pin "2") (pinfunction "2_2") (pintype "passive"))
      (node (ref "U10") (pin "7") (pinfunction "B_7") (pintype "passive"))
    )
    (net (code "118") (name "Net-(U11-ANODE)") (class "Default")
      (node (ref "R27") (pin "1") (pinfunction "1_1") (pintype "passive"))
      (node (ref "U11") (pin "2") (pinfunction "ANODE_2") (pintype "passive"))
    )
    (net (code "119") (name "Net-(U12-ANODE)") (class "Default")
      (node (ref "R28") (pin "1") (pinfunction "1_1") (pintype "passive"))
      (node (ref "U12") (pin "2") (pinfunction "ANODE_2") (pintype "passive"))
    )
    (net (code "120") (name "Net-(U13-ANODE)") (class "Default")
      (node (ref "R29") (pin "2") (pinfunction "2_2") (pintype "passive"))
      (node (ref "U13") (pin "2") (pinfunction "ANODE_2") (pintype "passive"))
    )
    (net (code "121") (name "Net-(U14-VCCIO)") (class "Default")
      (node (ref "R30") (pin "1") (pinfunction "1_1") (pintype "passive"))
      (node (ref "U14") (pin "8") (pinfunction "VCCIO_8") (pintype "passive"))
    )
    (net (code "122") (name "Net-(U15-EN)") (class "Default")
      (node (ref "R35") (pin "1") (pinfunction "1_1") (pintype "passive"))
      (node (ref "SW2") (pin "1") (pinfunction "1_1") (pintype "passive"))
      (node (ref "U15") (pin "3") (pinfunction "EN_3") (pintype "input"))
    )
    (net (code "123") (name "Net-(U15-IO0)") (class "Default")
      (node (ref "R34") (pin "1") (pinfunction "1_1") (pintype "passive"))
      (node (ref "SW1") (pin "2") (pinfunction "2_2") (pintype "passive"))
      (node (ref "U15") (pin "27") (pinfunction "IO0_27") (pintype "bidirectional"))
    )
    (net (code "124") (name "Net-(U15-IO1)") (class "Default")
      (node (ref "R37") (pin "2") (pinfunction "2_2") (pintype "passive"))
      (node (ref "U15") (pin "39") (pinfunction "IO1_39") (pintype "bidirectional"))
    )
    (net (code "125") (name "Net-(U15-IO4)") (class "Default")
      (node (ref "R36") (pin "2") (pinfunction "2_2") (pintype "passive"))
      (node (ref "U15") (pin "4") (pinfunction "IO4_4") (pintype "bidirectional"))
    )
    (net (code "126") (name "Net-(U18-ANODE)") (class "Default")
      (node (ref "R43") (pin "1") (pinfunction "1_1") (pintype "passive"))
      (node (ref "U18") (pin "2") (pinfunction "ANODE_2") (pintype "passive"))
    )
    (net (code "127") (name "Net-(U19-ANODE)") (class "Default")
      (node (ref "R44") (pin "2") (pinfunction "2_2") (pintype "passive"))
      (node (ref "U19") (pin "2") (pinfunction "ANODE_2") (pintype "passive"))
    )
    (net (code "128") (name "Net-(U20-ANODE)") (class "Default")
      (node (ref "R45") (pin "1") (pinfunction "1_1") (pintype "passive"))
      (node (ref "U20") (pin "2") (pinfunction "ANODE_2") (pintype "passive"))
    )
    (net (code "129") (name "Net-(U23-ANODE)") (class "Default")
      (node (ref "R51") (pin "1") (pinfunction "1_1") (pintype "passive"))
      (node (ref "U23") (pin "2") (pinfunction "ANODE_2") (pintype "passive"))
    )
    (net (code "130") (name "Net-(U24-ANODE)") (class "Default")
      (node (ref "R52") (pin "2") (pinfunction "2_2") (pintype "passive"))
      (node (ref "U24") (pin "2") (pinfunction "ANODE_2") (pintype "passive"))
    )
    (net (code "131") (name "Net-(U25-ANODE)") (class "Default")
      (node (ref "R53") (pin "1") (pinfunction "1_1") (pintype "passive"))
      (node (ref "U25") (pin "2") (pinfunction "ANODE_2") (pintype "passive"))
    )
    (net (code "132") (name "Net-(U28-ANODE)") (class "Default")
      (node (ref "R59") (pin "1") (pinfunction "1_1") (pintype "passive"))
      (node (ref "U28") (pin "2") (pinfunction "ANODE_2") (pintype "passive"))
    )
    (net (code "133") (name "Net-(U29-ANODE)") (class "Default")
      (node (ref "R60") (pin "2") (pinfunction "2_2") (pintype "passive"))
      (node (ref "U29") (pin "2") (pinfunction "ANODE_2") (pintype "passive"))
    )
    (net (code "134") (name "Net-(U30-ANODE)") (class "Default")
      (node (ref "R61") (pin "1") (pinfunction "1_1") (pintype "passive"))
      (node (ref "U30") (pin "2") (pinfunction "ANODE_2") (pintype "passive"))
    )
    (net (code "135") (name "Net-(U33-ANODE)") (class "Default")
      (node (ref "R67") (pin "1") (pinfunction "1_1") (pintype "passive"))
      (node (ref "U33") (pin "2") (pinfunction "ANODE_2") (pintype "passive"))
    )
    (net (code "136") (name "Net-(U34-ANODE)") (class "Default")
      (node (ref "R68") (pin "2") (pinfunction "2_2") (pintype "passive"))
      (node (ref "U34") (pin "2") (pinfunction "ANODE_2") (pintype "passive"))
    )
    (net (code "137") (name "Net-(U35-ANODE)") (class "Default")
      (node (ref "R69") (pin "1") (pinfunction "1_1") (pintype "passive"))
      (node (ref "U35") (pin "2") (pinfunction "ANODE_2") (pintype "passive"))
    )
    (net (code "138") (name "VBUS") (class "Default")
      (node (ref "D4") (pin "1") (pinfunction "A_1") (pintype "passive"))
      (node (ref "D7") (pin "1") (pinfunction "A_1") (pintype "passive"))
      (node (ref "J2") (pin "A4_B9") (pinfunction "VBUS_A4_B9") (pintype "power_in"))
      (node (ref "J2") (pin "B4_A9") (pinfunction "VBUS_B4_A9") (pintype "power_in"))
      (node (ref "U2") (pin "5") (pinfunction "VBUS_5") (pintype "power_in"))
    )
    (net (code "139") (name "VCC1") (class "Default")
      (node (ref "C33") (pin "2") (pinfunction "2_2") (pintype "passive"))
      (node (ref "C35") (pin "1") (pinfunction "1_1") (pintype "passive"))
      (node (ref "C36") (pin "2") (pinfunction "2_2") (pintype "passive"))
      (node (ref "C38") (pin "2") (pinfunction "2_2") (pintype "passive"))
      (node (ref "R38") (pin "2") (pinfunction "2_2") (pintype "passive"))
      (node (ref "R40") (pin "2") (pinfunction "2_2") (pintype "passive"))
      (node (ref "R42") (pin "2") (pinfunction "2_2") (pintype "passive"))
      (node (ref "R44") (pin "1") (pinfunction "1_1") (pintype "passive"))
      (node (ref "U16") (pin "4") (pinfunction "Vout_4") (pintype "passive"))
      (node (ref "U17") (pin "1") (pinfunction "VREF_1") (pintype "passive"))
      (node (ref "U17") (pin "8") (pinfunction "VCC_8") (pintype "passive"))
      (node (ref "U18") (pin "7") (pinfunction "V0_7") (pintype "passive"))
      (node (ref "U18") (pin "8") (pinfunction "VCC_8") (pintype "passive"))
      (node (ref "U20") (pin "7") (pinfunction "V0_7") (pintype "passive"))
      (node (ref "U20") (pin "8") (pinfunction "VCC_8") (pintype "passive"))
    )
    (net (code "140") (name "VCC2") (class "Default")
      (node (ref "C39") (pin "2") (pinfunction "2_2") (pintype "passive"))
      (node (ref "C41") (pin "1") (pinfunction "1_1") (pintype "passive"))
      (node (ref "C42") (pin "2") (pinfunction "2_2") (pintype "passive"))
      (node (ref "C44") (pin "2") (pinfunction "2_2") (pintype "passive"))
      (node (ref "R46") (pin "2") (pinfunction "2_2") (pintype "passive"))
      (node (ref "R48") (pin "2") (pinfunction "2_2") (pintype "passive"))
      (node (ref "R50") (pin "2") (pinfunction "2_2") (pintype "passive"))
      (node (ref "U21") (pin "4") (pinfunction "Vout_4") (pintype "passive"))
      (node (ref "U22") (pin "1") (pinfunction "VREF_1") (pintype "passive"))
      (node (ref "U22") (pin "8") (pinfunction "VCC_8") (pintype "passive"))
      (node (ref "U23") (pin "7") (pinfunction "V0_7") (pintype "passive"))
      (node (ref "U23") (pin "8") (pinfunction "VCC_8") (pintype "passive"))
      (node (ref "U25") (pin "7") (pinfunction "V0_7") (pintype "passive"))
      (node (ref "U25") (pin "8") (pinfunction "VCC_8") (pintype "passive"))
    )
    (net (code "141") (name "VCC3") (class "Default")
      (node (ref "C45") (pin "2") (pinfunction "2_2") (pintype "passive"))
      (node (ref "C47") (pin "1") (pinfunction "1_1") (pintype "passive"))
      (node (ref "C48") (pin "2") (pinfunction "2_2") (pintype "passive"))
      (node (ref "C50") (pin "2") (pinfunction "2_2") (pintype "passive"))
      (node (ref "R54") (pin "2") (pinfunction "2_2") (pintype "passive"))
      (node (ref "R56") (pin "2") (pinfunction "2_2") (pintype "passive"))
      (node (ref "R58") (pin "2") (pinfunction "2_2") (pintype "passive"))
      (node (ref "U26") (pin "4") (pinfunction "Vout_4") (pintype "passive"))
      (node (ref "U27") (pin "1") (pinfunction "VREF_1") (pintype "passive"))
      (node (ref "U27") (pin "8") (pinfunction "VCC_8") (pintype "passive"))
      (node (ref "U28") (pin "7") (pinfunction "V0_7") (pintype "passive"))
      (node (ref "U28") (pin "8") (pinfunction "VCC_8") (pintype "passive"))
      (node (ref "U30") (pin "7") (pinfunction "V0_7") (pintype "passive"))
      (node (ref "U30") (pin "8") (pinfunction "VCC_8") (pintype "passive"))
    )
    (net (code "142") (name "VCC4") (class "Default")
      (node (ref "C51") (pin "2") (pinfunction "2_2") (pintype "passive"))
      (node (ref "C53") (pin "1") (pinfunction "1_1") (pintype "passive"))
      (node (ref "C54") (pin "2") (pinfunction "2_2") (pintype "passive"))
      (node (ref "C56") (pin "2") (pinfunction "2_2") (pintype "passive"))
      (node (ref "R62") (pin "2") (pinfunction "2_2") (pintype "passive"))
      (node (ref "R64") (pin "2") (pinfunction "2_2") (pintype "passive"))
      (node (ref "R66") (pin "2") (pinfunction "2_2") (pintype "passive"))
      (node (ref "U31") (pin "4") (pinfunction "Vout_4") (pintype "passive"))
      (node (ref "U32") (pin "1") (pinfunction "VREF_1") (pintype "passive"))
      (node (ref "U32") (pin "8") (pinfunction "VCC_8") (pintype "passive"))
      (node (ref "U33") (pin "7") (pinfunction "V0_7") (pintype "passive"))
      (node (ref "U33") (pin "8") (pinfunction "VCC_8") (pintype "passive"))
      (node (ref "U35") (pin "7") (pinfunction "V0_7") (pintype "passive"))
      (node (ref "U35") (pin "8") (pinfunction "VCC_8") (pintype "passive"))
    )
    (net (code "143") (name "unconnected-(J2-SBU1-PadA8)") (class "Default")
      (node (ref "J2") (pin "A8") (pinfunction "SBU1_A8") (pintype "passive"))
    )
    (net (code "144") (name "unconnected-(J2-SBU2-PadB8)") (class "Default")
      (node (ref "J2") (pin "B8") (pinfunction "SBU2_B8") (pintype "passive"))
    )
    (net (code "145") (name "unconnected-(J3-Pad1)") (class "Default")
      (node (ref "J3") (pin "1") (pinfunction "1_1") (pintype "passive"))
    )
    (net (code "146") (name "unconnected-(J3-Pad4)") (class "Default")
      (node (ref "J3") (pin "4") (pinfunction "4_4") (pintype "passive"))
    )
    (net (code "147") (name "unconnected-(J3-Pad6)") (class "Default")
      (node (ref "J3") (pin "6") (pinfunction "6_6") (pintype "passive"))
    )
    (net (code "148") (name "unconnected-(J3-Pad7)") (class "Default")
      (node (ref "J3") (pin "7") (pinfunction "7_7") (pintype "passive"))
    )
    (net (code "149") (name "unconnected-(J3-Pad8)") (class "Default")
      (node (ref "J3") (pin "8") (pinfunction "8_8") (pintype "passive"))
    )
    (net (code "150") (name "unconnected-(J3-Pad9)") (class "Default")
      (node (ref "J3") (pin "9") (pinfunction "9_9") (pintype "passive"))
    )
    (net (code "151") (name "unconnected-(J5-NC-Pad7)") (class "Default")
      (node (ref "J5") (pin "7") (pinfunction "NC_7") (pintype "passive"))
    )
    (net (code "152") (name "unconnected-(R52-Pad1)") (class "Default")
      (node (ref "R52") (pin "1") (pinfunction "1_1") (pintype "passive"))
    )
    (net (code "153") (name "unconnected-(R60-Pad1)") (class "Default")
      (node (ref "R60") (pin "1") (pinfunction "1_1") (pintype "passive"))
    )
    (net (code "154") (name "unconnected-(R68-Pad1)") (class "Default")
      (node (ref "R68") (pin "1") (pinfunction "1_1") (pintype "passive"))
    )
    (net (code "155") (name "unconnected-(U3-PadEPAD)") (class "Default")
      (node (ref "U3") (pin "EPAD") (pinfunction "EPAD_EPAD") (pintype "power_in"))
    )
    (net (code "156") (name "unconnected-(U4-GND-Pad2)") (class "Default")
      (node (ref "U4") (pin "2") (pinfunction "GND_2") (pintype "power_in"))
    )
    (net (code "157") (name "unconnected-(U6-NC-Pad1)") (class "Default")
      (node (ref "U6") (pin "1") (pinfunction "NC_1") (pintype "passive"))
    )
    (net (code "158") (name "unconnected-(U6-NC-Pad4)") (class "Default")
      (node (ref "U6") (pin "4") (pinfunction "NC_4") (pintype "passive"))
    )
    (net (code "159") (name "unconnected-(U7-R2IN-Pad8)") (class "Default")
      (node (ref "U7") (pin "8") (pinfunction "R2IN_8") (pintype "input+no_connect"))
    )
    (net (code "160") (name "unconnected-(U7-R2OUT-Pad9)") (class "Default")
      (node (ref "U7") (pin "9") (pinfunction "R2OUT_9") (pintype "output+no_connect"))
    )
    (net (code "161") (name "unconnected-(U7-T2IN-Pad10)") (class "Default")
      (node (ref "U7") (pin "10") (pinfunction "T2IN_10") (pintype "input+no_connect"))
    )
    (net (code "162") (name "unconnected-(U7-T2OUT-Pad7)") (class "Default")
      (node (ref "U7") (pin "7") (pinfunction "T2OUT_7") (pintype "output"))
    )
    (net (code "163") (name "unconnected-(U8-NC-Pad1)") (class "Default")
      (node (ref "U8") (pin "1") (pinfunction "NC_1") (pintype "passive"))
    )
    (net (code "164") (name "unconnected-(U8-NC-Pad4)") (class "Default")
      (node (ref "U8") (pin "4") (pinfunction "NC_4") (pintype "passive"))
    )
    (net (code "165") (name "unconnected-(U11-NC-Pad1)") (class "Default")
      (node (ref "U11") (pin "1") (pinfunction "NC_1") (pintype "passive"))
    )
    (net (code "166") (name "unconnected-(U11-NC-Pad4)") (class "Default")
      (node (ref "U11") (pin "4") (pinfunction "NC_4") (pintype "passive"))
    )
    (net (code "167") (name "unconnected-(U12-NC-Pad1)") (class "Default")
      (node (ref "U12") (pin "1") (pinfunction "NC_1") (pintype "passive"))
    )
    (net (code "168") (name "unconnected-(U12-NC-Pad4)") (class "Default")
      (node (ref "U12") (pin "4") (pinfunction "NC_4") (pintype "passive"))
    )
    (net (code "169") (name "unconnected-(U13-NC-Pad1)") (class "Default")
      (node (ref "U13") (pin "1") (pinfunction "NC_1") (pintype "passive"))
    )
    (net (code "170") (name "unconnected-(U13-NC-Pad4)") (class "Default")
      (node (ref "U13") (pin "4") (pinfunction "NC_4") (pintype "passive"))
    )
    (net (code "171") (name "unconnected-(U14-CTS-Pad15)") (class "Default")
      (node (ref "U14") (pin "15") (pinfunction "CTS_15") (pintype "passive"))
    )
    (net (code "172") (name "unconnected-(U14-RTS{slash}TNOW1-Pad16)") (class "Default")
      (node (ref "U14") (pin "16") (pinfunction "RTS/TNOW1_16") (pintype "passive"))
    )
    (net (code "173") (name "unconnected-(U14-RXD2-Pad10)") (class "Default")
      (node (ref "U14") (pin "10") (pinfunction "RXD2_10") (pintype "passive"))
    )
    (net (code "174") (name "unconnected-(U14-TNOW2-Pad12)") (class "Default")
      (node (ref "U14") (pin "12") (pinfunction "TNOW2_12") (pintype "passive"))
    )
    (net (code "175") (name "unconnected-(U14-TXD2-Pad9)") (class "Default")
      (node (ref "U14") (pin "9") (pinfunction "TXD2_9") (pintype "passive"))
    )
    (net (code "176") (name "unconnected-(U15-IO3-Pad15)") (class "Default")
      (node (ref "U15") (pin "15") (pinfunction "IO3_15") (pintype "bidirectional+no_connect"))
    )
    (net (code "177") (name "unconnected-(U15-IO8-Pad12)") (class "Default")
      (node (ref "U15") (pin "12") (pinfunction "IO8_12") (pintype "bidirectional+no_connect"))
    )
    (net (code "178") (name "unconnected-(U15-IO9-Pad17)") (class "Default")
      (node (ref "U15") (pin "17") (pinfunction "IO9_17") (pintype "bidirectional+no_connect"))
    )
    (net (code "179") (name "unconnected-(U15-IO10-Pad18)") (class "Default")
      (node (ref "U15") (pin "18") (pinfunction "IO10_18") (pintype "bidirectional+no_connect"))
    )
    (net (code "180") (name "unconnected-(U15-IO11-Pad19)") (class "Default")
      (node (ref "U15") (pin "19") (pinfunction "IO11_19") (pintype "bidirectional+no_connect"))
    )
    (net (code "181") (name "unconnected-(U15-IO12-Pad20)") (class "Default")
      (node (ref "U15") (pin "20") (pinfunction "IO12_20") (pintype "bidirectional+no_connect"))
    )
    (net (code "182") (name "unconnected-(U15-IO18-Pad11)") (class "Default")
      (node (ref "U15") (pin "11") (pinfunction "IO18_11") (pintype "bidirectional+no_connect"))
    )
    (net (code "183") (name "unconnected-(U15-IO35-Pad28)") (class "Default")
      (node (ref "U15") (pin "28") (pinfunction "IO35_28") (pintype "bidirectional+no_connect"))
    )
    (net (code "184") (name "unconnected-(U15-IO36-Pad29)") (class "Default")
      (node (ref "U15") (pin "29") (pinfunction "IO36_29") (pintype "bidirectional+no_connect"))
    )
    (net (code "185") (name "unconnected-(U15-IO37-Pad30)") (class "Default")
      (node (ref "U15") (pin "30") (pinfunction "IO37_30") (pintype "bidirectional+no_connect"))
    )
    (net (code "186") (name "unconnected-(U15-IO46-Pad16)") (class "Default")
      (node (ref "U15") (pin "16") (pinfunction "IO46_16") (pintype "bidirectional"))
    )
    (net (code "187") (name "unconnected-(U18-NC-Pad1)") (class "Default")
      (node (ref "U18") (pin "1") (pinfunction "NC_1") (pintype "passive"))
    )
    (net (code "188") (name "unconnected-(U18-NC-Pad4)") (class "Default")
      (node (ref "U18") (pin "4") (pinfunction "NC_4") (pintype "passive"))
    )
    (net (code "189") (name "unconnected-(U19-NC-Pad1)") (class "Default")
      (node (ref "U19") (pin "1") (pinfunction "NC_1") (pintype "passive"))
    )
    (net (code "190") (name "unconnected-(U20-NC-Pad1)") (class "Default")
      (node (ref "U20") (pin "1") (pinfunction "NC_1") (pintype "passive"))
    )
    (net (code "191") (name "unconnected-(U20-NC-Pad4)") (class "Default")
      (node (ref "U20") (pin "4") (pinfunction "NC_4") (pintype "passive"))
    )
    (net (code "192") (name "unconnected-(U23-NC-Pad1)") (class "Default")
      (node (ref "U23") (pin "1") (pinfunction "NC_1") (pintype "passive"))
    )
    (net (code "193") (name "unconnected-(U23-NC-Pad4)") (class "Default")
      (node (ref "U23") (pin "4") (pinfunction "NC_4") (pintype "passive"))
    )
    (net (code "194") (name "unconnected-(U24-NC-Pad1)") (class "Default")
      (node (ref "U24") (pin "1") (pinfunction "NC_1") (pintype "passive"))
    )
    (net (code "195") (name "unconnected-(U25-NC-Pad1)") (class "Default")
      (node (ref "U25") (pin "1") (pinfunction "NC_1") (pintype "passive"))
    )
    (net (code "196") (name "unconnected-(U25-NC-Pad4)") (class "Default")
      (node (ref "U25") (pin "4") (pinfunction "NC_4") (pintype "passive"))
    )
    (net (code "197") (name "unconnected-(U28-NC-Pad1)") (class "Default")
      (node (ref "U28") (pin "1") (pinfunction "NC_1") (pintype "passive"))
    )
    (net (code "198") (name "unconnected-(U28-NC-Pad4)") (class "Default")
      (node (ref "U28") (pin "4") (pinfunction "NC_4") (pintype "passive"))
    )
    (net (code "199") (name "unconnected-(U29-NC-Pad1)") (class "Default")
      (node (ref "U29") (pin "1") (pinfunction "NC_1") (pintype "passive"))
    )
    (net (code "200") (name "unconnected-(U30-NC-Pad1)") (class "Default")
      (node (ref "U30") (pin "1") (pinfunction "NC_1") (pintype "passive"))
    )
    (net (code "201") (name "unconnected-(U30-NC-Pad4)") (class "Default")
      (node (ref "U30") (pin "4") (pinfunction "NC_4") (pintype "passive"))
    )
    (net (code "202") (name "unconnected-(U33-NC-Pad1)") (class "Default")
      (node (ref "U33") (pin "1") (pinfunction "NC_1") (pintype "passive"))
    )
    (net (code "203") (name "unconnected-(U33-NC-Pad4)") (class "Default")
      (node (ref "U33") (pin "4") (pinfunction "NC_4") (pintype "passive"))
    )
    (net (code "204") (name "unconnected-(U34-NC-Pad1)") (class "Default")
      (node (ref "U34") (pin "1") (pinfunction "NC_1") (pintype "passive"))
    )
    (net (code "205") (name "unconnected-(U34-NC-Pad4)") (class "Default")
      (node (ref "U34") (pin "4") (pinfunction "NC_4") (pintype "passive"))
    )
    (net (code "206") (name "unconnected-(U35-NC-Pad1)") (class "Default")
      (node (ref "U35") (pin "1") (pinfunction "NC_1") (pintype "passive"))
    )
    (net (code "207") (name "unconnected-(U35-NC-Pad4)") (class "Default")
      (node (ref "U35") (pin "4") (pinfunction "NC_4") (pintype "passive"))
    )
  )
)
